# PP-Rev2.net
KiCad netlist of a schematic drawn in EAGLE
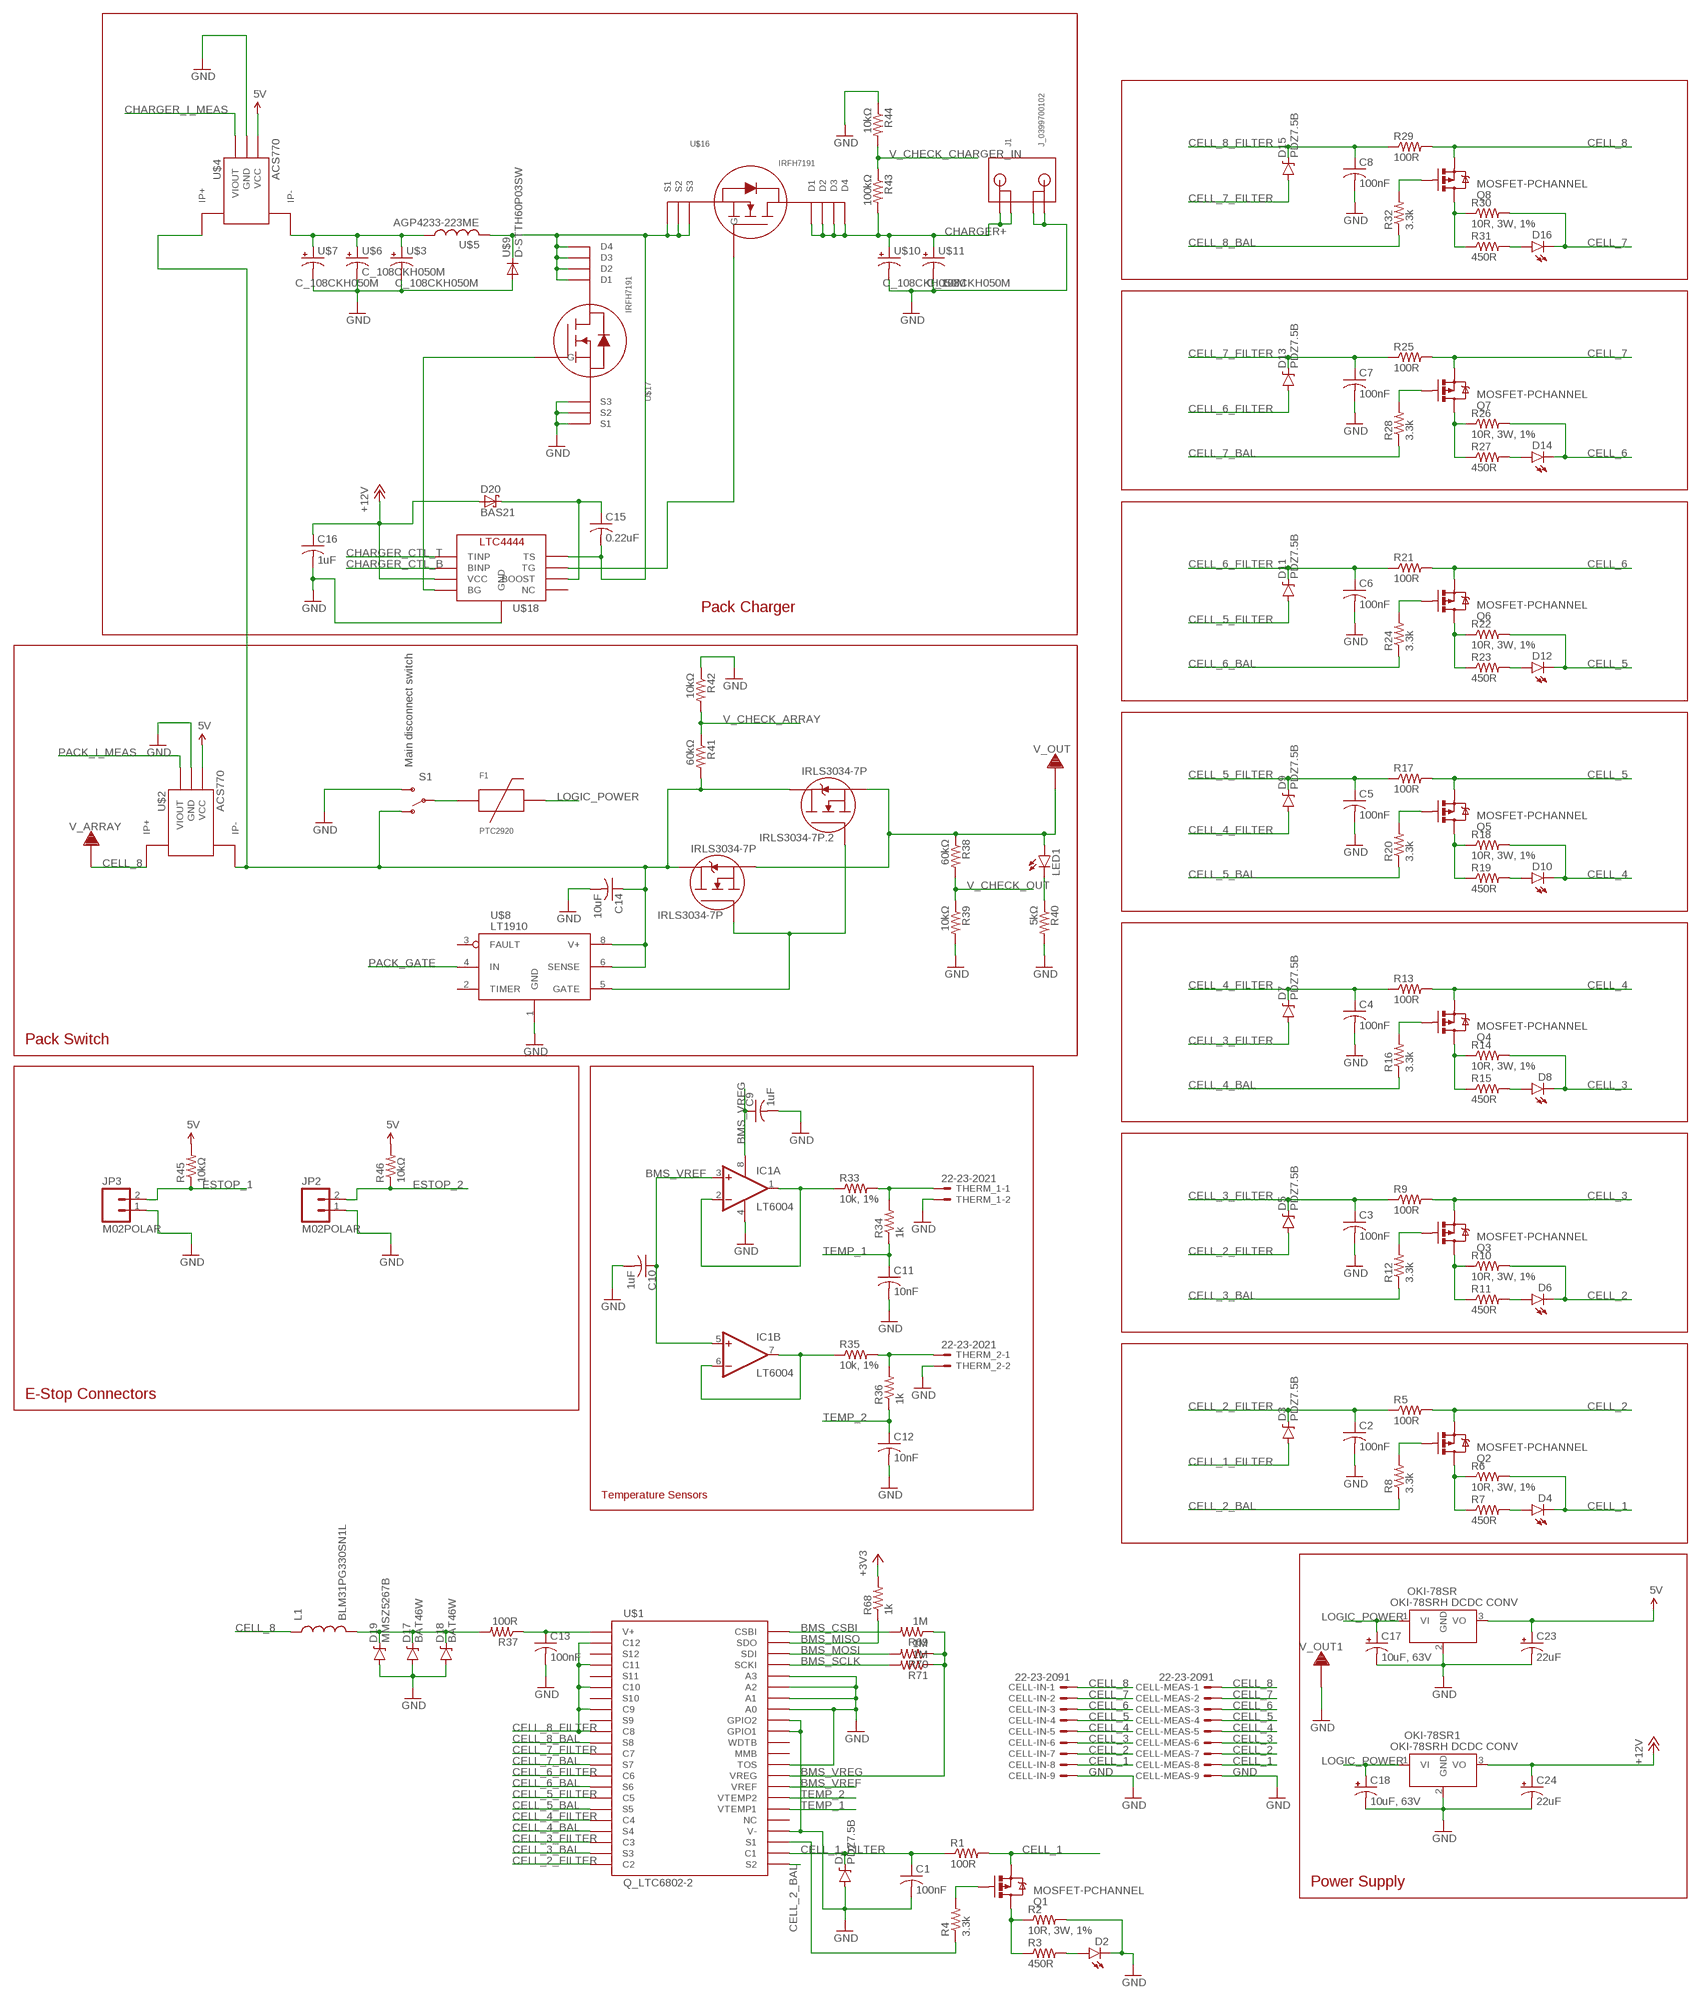
[diagram p0: schematic, sheet 1, part 1 of 2]
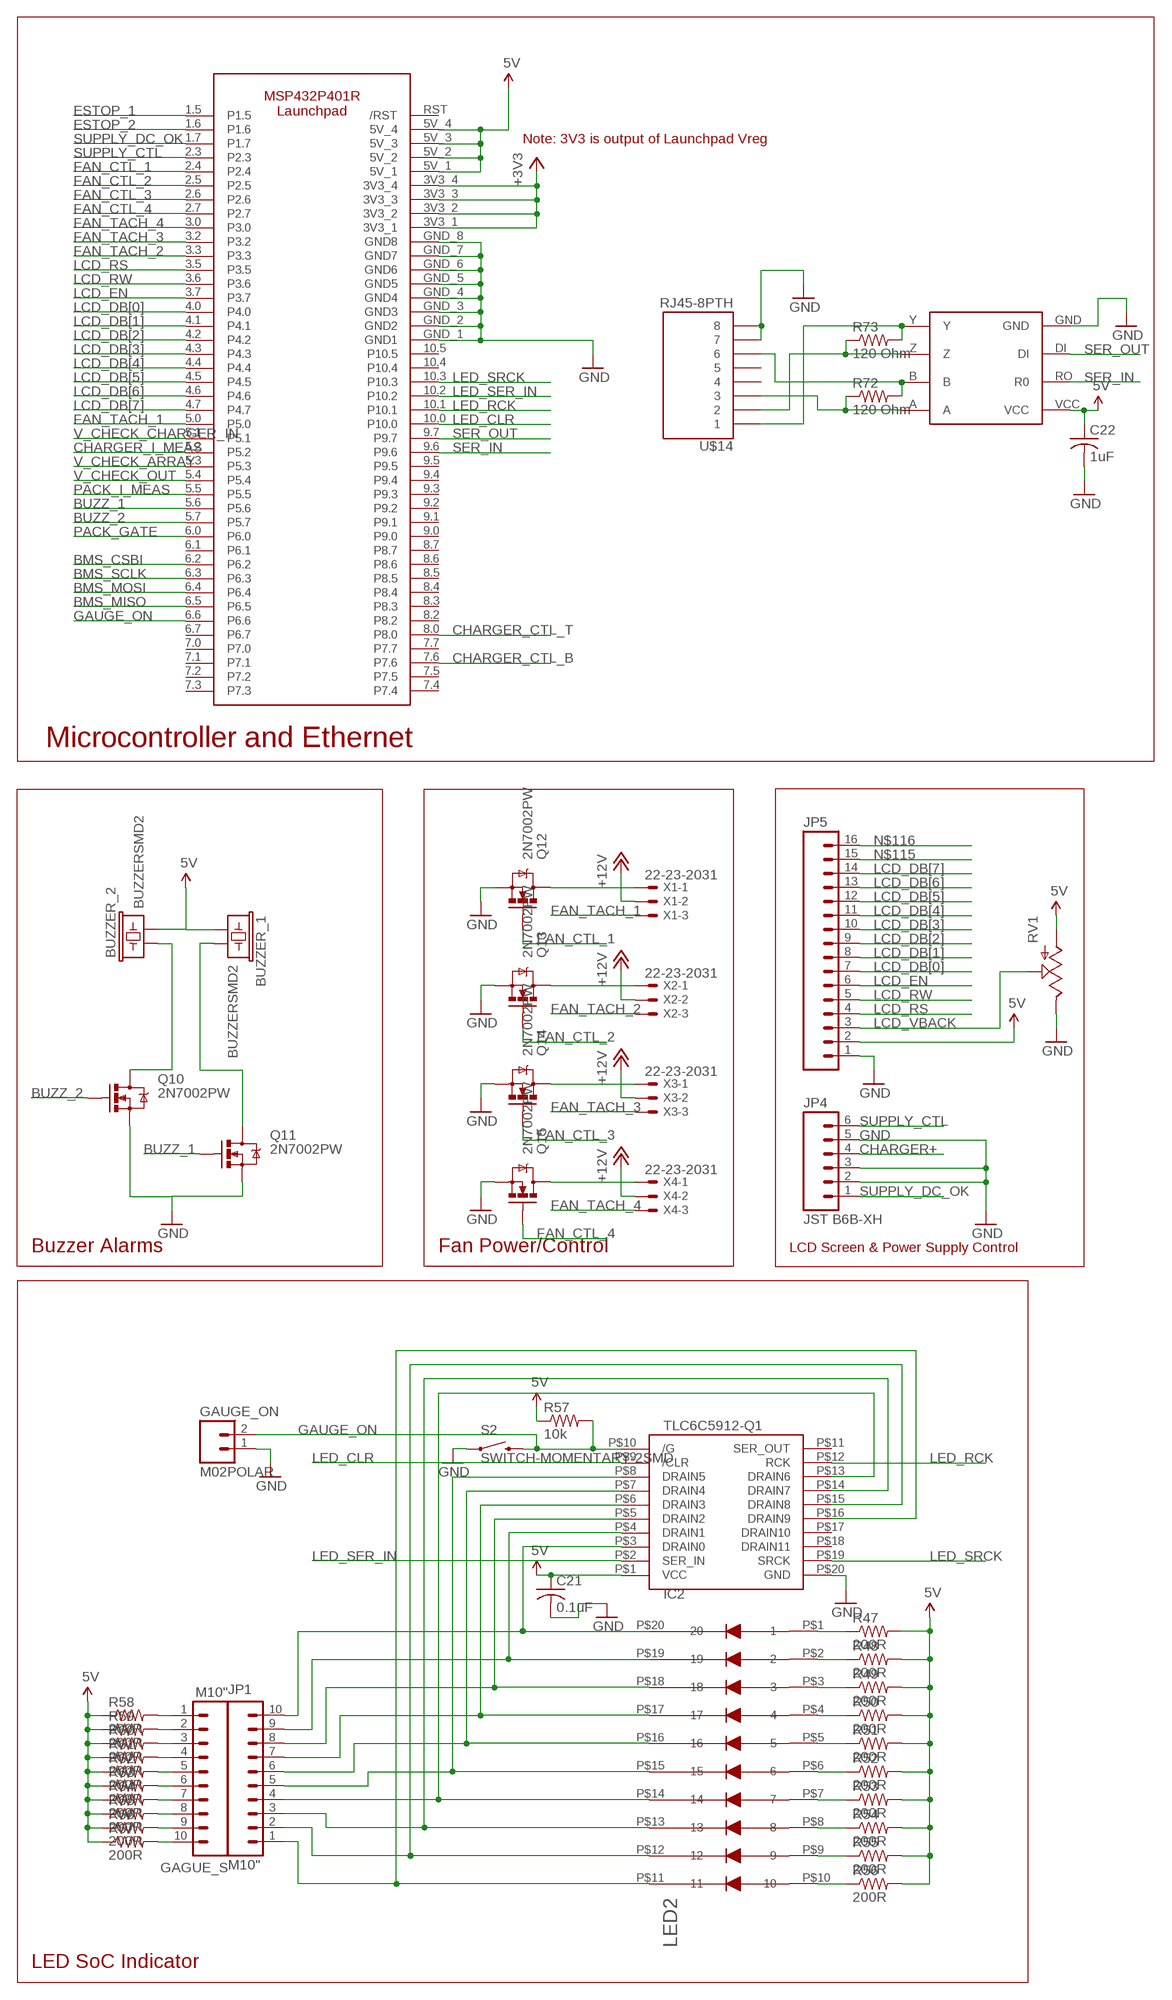
[diagram p1: schematic, sheet 1, part 2 of 2]

(export (version "E")
  (design (tool "Eeschema 10.0.6"))
  (components
    (comp (ref "BUZZER_1")
      (value "BUZZERSMD2")
      (footprint "eagle-import:BUZZER-CCV")
      (libsource (lib "eagle-import") (part "BUZZERSMD2"))
    )
    (comp (ref "BUZZER_2")
      (value "BUZZERSMD2")
      (footprint "eagle-import:BUZZER-CCV")
      (libsource (lib "eagle-import") (part "BUZZERSMD2"))
    )
    (comp (ref "C1")
      (value "100nF")
      (footprint "eagle-import:C1206")
      (libsource (lib "eagle-import") (part "C-USC1206"))
    )
    (comp (ref "C2")
      (value "100nF")
      (footprint "eagle-import:C1206")
      (libsource (lib "eagle-import") (part "C-USC1206"))
    )
    (comp (ref "C3")
      (value "100nF")
      (footprint "eagle-import:C1206")
      (libsource (lib "eagle-import") (part "C-USC1206"))
    )
    (comp (ref "C4")
      (value "100nF")
      (footprint "eagle-import:C1206")
      (libsource (lib "eagle-import") (part "C-USC1206"))
    )
    (comp (ref "C5")
      (value "100nF")
      (footprint "eagle-import:C1206")
      (libsource (lib "eagle-import") (part "C-USC1206"))
    )
    (comp (ref "C6")
      (value "100nF")
      (footprint "eagle-import:C1206")
      (libsource (lib "eagle-import") (part "C-USC1206"))
    )
    (comp (ref "C7")
      (value "100nF")
      (footprint "eagle-import:C1206")
      (libsource (lib "eagle-import") (part "C-USC1206"))
    )
    (comp (ref "C8")
      (value "100nF")
      (footprint "eagle-import:C1206")
      (libsource (lib "eagle-import") (part "C-USC1206"))
    )
    (comp (ref "C9")
      (value "1uF")
      (footprint "eagle-import:C1206")
      (libsource (lib "eagle-import") (part "C-USC1206"))
    )
    (comp (ref "C10")
      (value "1uF")
      (footprint "eagle-import:C1206")
      (libsource (lib "eagle-import") (part "C-USC1206"))
    )
    (comp (ref "C11")
      (value "10nF")
      (footprint "eagle-import:C1206")
      (libsource (lib "eagle-import") (part "C-USC1206"))
    )
    (comp (ref "C12")
      (value "10nF")
      (footprint "eagle-import:C1206")
      (libsource (lib "eagle-import") (part "C-USC1206"))
    )
    (comp (ref "C13")
      (value "100nF")
      (footprint "eagle-import:C1206")
      (libsource (lib "eagle-import") (part "C-USC1206"))
    )
    (comp (ref "C14")
      (value "10uF")
      (footprint "eagle-import:C1206")
      (libsource (lib "eagle-import") (part "C-USC1206"))
    )
    (comp (ref "C15")
      (value "0.22uF")
      (footprint "eagle-import:C1206")
      (libsource (lib "eagle-import") (part "C-USC1206"))
    )
    (comp (ref "C16")
      (value "1uF")
      (footprint "eagle-import:C1206")
      (libsource (lib "eagle-import") (part "C-USC1206"))
    )
    (comp (ref "C17")
      (value "10uF, 63V")
      (footprint "eagle-import:PANASONIC_D")
      (libsource (lib "eagle-import") (part "CPOL-USD"))
    )
    (comp (ref "C18")
      (value "10uF, 63V")
      (footprint "eagle-import:PANASONIC_D")
      (libsource (lib "eagle-import") (part "CPOL-USD"))
    )
    (comp (ref "C21")
      (value "0.1uF")
      (footprint "eagle-import:C1206")
      (libsource (lib "eagle-import") (part "resistor_C-USC1206"))
    )
    (comp (ref "C22")
      (value "1uF")
      (footprint "eagle-import:C1206")
      (libsource (lib "eagle-import") (part "resistor_C-USC1206"))
    )
    (comp (ref "C23")
      (value "22uF")
      (footprint "eagle-import:PANASONIC_D")
      (libsource (lib "eagle-import") (part "CPOL-USD"))
    )
    (comp (ref "C24")
      (value "22uF")
      (footprint "eagle-import:PANASONIC_D")
      (libsource (lib "eagle-import") (part "CPOL-USD"))
    )
    (comp (ref "CELL-IN")
      (value "22-23-2091")
      (footprint "eagle-import:22-23-2091")
      (fields (field (name "MF") "MOLEX"))
      (libsource (lib "eagle-import") (part "22-23-2091"))
    )
    (comp (ref "CELL-MEAS")
      (value "22-23-2091")
      (footprint "eagle-import:22-23-2091")
      (fields (field (name "MF") "MOLEX"))
      (libsource (lib "eagle-import") (part "22-23-2091"))
    )
    (comp (ref "D1")
      (value "PDZ7.5B")
      (footprint "eagle-import:SOD-323")
      (libsource (lib "eagle-import") (part "DIODE-ZENER5.6V"))
    )
    (comp (ref "D2")
      (value "LED1206")
      (footprint "eagle-import:LED-1206")
      (libsource (lib "eagle-import") (part "LED1206"))
    )
    (comp (ref "D3")
      (value "PDZ7.5B")
      (footprint "eagle-import:SOD-323")
      (libsource (lib "eagle-import") (part "DIODE-ZENER5.6V"))
    )
    (comp (ref "D4")
      (value "LED1206")
      (footprint "eagle-import:LED-1206")
      (libsource (lib "eagle-import") (part "LED1206"))
    )
    (comp (ref "D5")
      (value "PDZ7.5B")
      (footprint "eagle-import:SOD-323")
      (libsource (lib "eagle-import") (part "DIODE-ZENER5.6V"))
    )
    (comp (ref "D6")
      (value "LED1206")
      (footprint "eagle-import:LED-1206")
      (libsource (lib "eagle-import") (part "LED1206"))
    )
    (comp (ref "D7")
      (value "PDZ7.5B")
      (footprint "eagle-import:SOD-323")
      (libsource (lib "eagle-import") (part "DIODE-ZENER5.6V"))
    )
    (comp (ref "D8")
      (value "LED1206")
      (footprint "eagle-import:LED-1206")
      (libsource (lib "eagle-import") (part "LED1206"))
    )
    (comp (ref "D9")
      (value "PDZ7.5B")
      (footprint "eagle-import:SOD-323")
      (libsource (lib "eagle-import") (part "DIODE-ZENER5.6V"))
    )
    (comp (ref "D10")
      (value "LED1206")
      (footprint "eagle-import:LED-1206")
      (libsource (lib "eagle-import") (part "LED1206"))
    )
    (comp (ref "D11")
      (value "PDZ7.5B")
      (footprint "eagle-import:SOD-323")
      (libsource (lib "eagle-import") (part "DIODE-ZENER5.6V"))
    )
    (comp (ref "D12")
      (value "LED1206")
      (footprint "eagle-import:LED-1206")
      (libsource (lib "eagle-import") (part "LED1206"))
    )
    (comp (ref "D13")
      (value "PDZ7.5B")
      (footprint "eagle-import:SOD-323")
      (libsource (lib "eagle-import") (part "DIODE-ZENER5.6V"))
    )
    (comp (ref "D14")
      (value "LED1206")
      (footprint "eagle-import:LED-1206")
      (libsource (lib "eagle-import") (part "LED1206"))
    )
    (comp (ref "D15")
      (value "PDZ7.5B")
      (footprint "eagle-import:SOD-323")
      (libsource (lib "eagle-import") (part "DIODE-ZENER5.6V"))
    )
    (comp (ref "D16")
      (value "LED1206")
      (footprint "eagle-import:LED-1206")
      (libsource (lib "eagle-import") (part "LED1206"))
    )
    (comp (ref "D17")
      (value "BAT46W")
      (footprint "eagle-import:SOD-123")
      (libsource (lib "eagle-import") (part "DIODE-ZENER16V"))
    )
    (comp (ref "D18")
      (value "BAT46W")
      (footprint "eagle-import:SOD-123")
      (libsource (lib "eagle-import") (part "DIODE-ZENER16V"))
    )
    (comp (ref "D19")
      (value "MMSZ5267B")
      (footprint "eagle-import:SOD-123")
      (libsource (lib "eagle-import") (part "DIODE-ZENER16V"))
    )
    (comp (ref "D20")
      (value "BAS21")
      (footprint "eagle-import:SOT23")
      (libsource (lib "eagle-import") (part "BAS40"))
    )
    (comp (ref "F1")
      (value "PTC2920")
      (footprint "eagle-import:2920")
      (libsource (lib "eagle-import") (part "PTC2920"))
    )
    (comp (ref "GAGUE_S")
      (value "M10\"")
      (footprint "eagle-import:1X10")
      (libsource (lib "eagle-import") (part "M10{dblquote}"))
    )
    (comp (ref "GAUGE_ON")
      (value "M02POLAR")
      (footprint "eagle-import:MOLEX-1X2")
      (libsource (lib "eagle-import") (part "M02POLAR"))
    )
    (comp (ref "IC1")
      (value "LT6004")
      (footprint "eagle-import:MSOP08")
      (libsource (lib "eagle-import") (part "OPA2E345"))
    )
    (comp (ref "IC2")
      (value "TLC6C5912-Q1")
      (footprint "eagle-import:SOIC-20")
      (libsource (lib "eagle-import") (part "TLC6C5912-Q1"))
    )
    (comp (ref "IRLS3034-7P")
      (value "IRLS3034-7P")
      (footprint "eagle-import:D2PAK-7")
      (libsource (lib "eagle-import") (part "IRLS3034-7P"))
    )
    (comp (ref "IRLS3034-7P.2")
      (value "IRLS3034-7P")
      (footprint "eagle-import:D2PAK-7")
      (libsource (lib "eagle-import") (part "IRLS3034-7P"))
    )
    (comp (ref "J1")
      (value "J_0399700102")
      (footprint "eagle-import:J_2CONHC")
      (libsource (lib "eagle-import") (part "J_0399700102"))
    )
    (comp (ref "JP1")
      (value "M10\"")
      (footprint "eagle-import:1X10")
      (libsource (lib "eagle-import") (part "M10{dblquote}"))
    )
    (comp (ref "JP2")
      (value "M02POLAR")
      (footprint "eagle-import:MOLEX-1X2")
      (libsource (lib "eagle-import") (part "M02POLAR"))
    )
    (comp (ref "JP3")
      (value "M02POLAR")
      (footprint "eagle-import:MOLEX-1X2")
      (libsource (lib "eagle-import") (part "M02POLAR"))
    )
    (comp (ref "JP4")
      (value "JST B6B-XH")
      (footprint "eagle-import:MOLEX-1X6")
      (libsource (lib "eagle-import") (part "M06POLAR"))
    )
    (comp (ref "JP5")
      (value "M16LONGPADS")
      (footprint "eagle-import:1X16_LONGPADS")
      (libsource (lib "eagle-import") (part "M16LONGPADS"))
    )
    (comp (ref "L1")
      (value "BLM31PG330SN1L")
      (footprint "eagle-import:1210")
      (libsource (lib "eagle-import") (part "INDUCTOR1210"))
    )
    (comp (ref "LED1")
      (value "LED1206")
      (footprint "eagle-import:LED-1206")
      (libsource (lib "eagle-import") (part "LED1206"))
    )
    (comp (ref "LED2")
      (value "LED-DC7G3HWA")
      (footprint "eagle-import:LED-10")
      (libsource (lib "eagle-import") (part "LED-DC7G3HWA"))
    )
    (comp (ref "OKI-78SR")
      (value "Q_OKI-78SR5")
      (footprint "eagle-import:OKI-78SRH")
      (libsource (lib "eagle-import") (part "Q_OKI-78SR"))
    )
    (comp (ref "OKI-78SR1")
      (value "Q_OKI-78SR12")
      (footprint "eagle-import:OKI-78SRH")
      (libsource (lib "eagle-import") (part "Q_OKI-78SR"))
    )
    (comp (ref "Q1")
      (value "MOSFET-PCHANNEL")
      (footprint "eagle-import:SOT23-3")
      (libsource (lib "eagle-import") (part "MOSFET-PCHANNEL"))
    )
    (comp (ref "Q2")
      (value "MOSFET-PCHANNEL")
      (footprint "eagle-import:SOT23-3")
      (libsource (lib "eagle-import") (part "MOSFET-PCHANNEL"))
    )
    (comp (ref "Q3")
      (value "MOSFET-PCHANNEL")
      (footprint "eagle-import:SOT23-3")
      (libsource (lib "eagle-import") (part "MOSFET-PCHANNEL"))
    )
    (comp (ref "Q4")
      (value "MOSFET-PCHANNEL")
      (footprint "eagle-import:SOT23-3")
      (libsource (lib "eagle-import") (part "MOSFET-PCHANNEL"))
    )
    (comp (ref "Q5")
      (value "MOSFET-PCHANNEL")
      (footprint "eagle-import:SOT23-3")
      (libsource (lib "eagle-import") (part "MOSFET-PCHANNEL"))
    )
    (comp (ref "Q6")
      (value "MOSFET-PCHANNEL")
      (footprint "eagle-import:SOT23-3")
      (libsource (lib "eagle-import") (part "MOSFET-PCHANNEL"))
    )
    (comp (ref "Q7")
      (value "MOSFET-PCHANNEL")
      (footprint "eagle-import:SOT23-3")
      (libsource (lib "eagle-import") (part "MOSFET-PCHANNEL"))
    )
    (comp (ref "Q8")
      (value "MOSFET-PCHANNEL")
      (footprint "eagle-import:SOT23-3")
      (libsource (lib "eagle-import") (part "MOSFET-PCHANNEL"))
    )
    (comp (ref "Q10")
      (value "2N7002PW")
      (footprint "eagle-import:SOT323")
      (libsource (lib "eagle-import") (part "MOSFET-NCHANNEL2N7002PW"))
    )
    (comp (ref "Q11")
      (value "2N7002PW")
      (footprint "eagle-import:SOT323")
      (libsource (lib "eagle-import") (part "MOSFET-NCHANNEL2N7002PW"))
    )
    (comp (ref "Q12")
      (value "2N7002PW")
      (footprint "eagle-import:SOT323")
      (libsource (lib "eagle-import") (part "MOSFET-NCHANNEL2N7002PW"))
    )
    (comp (ref "Q13")
      (value "2N7002PW")
      (footprint "eagle-import:SOT323")
      (libsource (lib "eagle-import") (part "MOSFET-NCHANNEL2N7002PW"))
    )
    (comp (ref "Q14")
      (value "2N7002PW")
      (footprint "eagle-import:SOT323")
      (libsource (lib "eagle-import") (part "MOSFET-NCHANNEL2N7002PW"))
    )
    (comp (ref "Q15")
      (value "2N7002PW")
      (footprint "eagle-import:SOT323")
      (libsource (lib "eagle-import") (part "MOSFET-NCHANNEL2N7002PW"))
    )
    (comp (ref "R1")
      (value "100R")
      (footprint "eagle-import:R1206")
      (libsource (lib "eagle-import") (part "R-US_R1206"))
    )
    (comp (ref "R2")
      (value "10R, 3W, 1%")
      (footprint "eagle-import:AXIAL-0.6")
      (libsource (lib "eagle-import") (part "SparkFun-Resistors_RESISTORPTH-1W"))
    )
    (comp (ref "R3")
      (value "450R")
      (footprint "eagle-import:1206")
      (libsource (lib "eagle-import") (part "SparkFun-Resistors_RESISTOR1206"))
    )
    (comp (ref "R4")
      (value "3.3k")
      (footprint "eagle-import:1206")
      (libsource (lib "eagle-import") (part "SparkFun-Resistors_RESISTOR1206"))
    )
    (comp (ref "R5")
      (value "100R")
      (footprint "eagle-import:R1206")
      (libsource (lib "eagle-import") (part "R-US_R1206"))
    )
    (comp (ref "R6")
      (value "10R, 3W, 1%")
      (footprint "eagle-import:AXIAL-0.6")
      (libsource (lib "eagle-import") (part "SparkFun-Resistors_RESISTORPTH-1W"))
    )
    (comp (ref "R7")
      (value "450R")
      (footprint "eagle-import:1206")
      (libsource (lib "eagle-import") (part "SparkFun-Resistors_RESISTOR1206"))
    )
    (comp (ref "R8")
      (value "3.3k")
      (footprint "eagle-import:1206")
      (libsource (lib "eagle-import") (part "SparkFun-Resistors_RESISTOR1206"))
    )
    (comp (ref "R9")
      (value "100R")
      (footprint "eagle-import:R1206")
      (libsource (lib "eagle-import") (part "R-US_R1206"))
    )
    (comp (ref "R10")
      (value "10R, 3W, 1%")
      (footprint "eagle-import:AXIAL-0.6")
      (libsource (lib "eagle-import") (part "SparkFun-Resistors_RESISTORPTH-1W"))
    )
    (comp (ref "R11")
      (value "450R")
      (footprint "eagle-import:1206")
      (libsource (lib "eagle-import") (part "SparkFun-Resistors_RESISTOR1206"))
    )
    (comp (ref "R12")
      (value "3.3k")
      (footprint "eagle-import:1206")
      (libsource (lib "eagle-import") (part "SparkFun-Resistors_RESISTOR1206"))
    )
    (comp (ref "R13")
      (value "100R")
      (footprint "eagle-import:R1206")
      (libsource (lib "eagle-import") (part "R-US_R1206"))
    )
    (comp (ref "R14")
      (value "10R, 3W, 1%")
      (footprint "eagle-import:AXIAL-0.6")
      (libsource (lib "eagle-import") (part "SparkFun-Resistors_RESISTORPTH-1W"))
    )
    (comp (ref "R15")
      (value "450R")
      (footprint "eagle-import:1206")
      (libsource (lib "eagle-import") (part "SparkFun-Resistors_RESISTOR1206"))
    )
    (comp (ref "R16")
      (value "3.3k")
      (footprint "eagle-import:1206")
      (libsource (lib "eagle-import") (part "SparkFun-Resistors_RESISTOR1206"))
    )
    (comp (ref "R17")
      (value "100R")
      (footprint "eagle-import:R1206")
      (libsource (lib "eagle-import") (part "R-US_R1206"))
    )
    (comp (ref "R18")
      (value "10R, 3W, 1%")
      (footprint "eagle-import:AXIAL-0.6")
      (libsource (lib "eagle-import") (part "SparkFun-Resistors_RESISTORPTH-1W"))
    )
    (comp (ref "R19")
      (value "450R")
      (footprint "eagle-import:1206")
      (libsource (lib "eagle-import") (part "SparkFun-Resistors_RESISTOR1206"))
    )
    (comp (ref "R20")
      (value "3.3k")
      (footprint "eagle-import:1206")
      (libsource (lib "eagle-import") (part "SparkFun-Resistors_RESISTOR1206"))
    )
    (comp (ref "R21")
      (value "100R")
      (footprint "eagle-import:R1206")
      (libsource (lib "eagle-import") (part "R-US_R1206"))
    )
    (comp (ref "R22")
      (value "10R, 3W, 1%")
      (footprint "eagle-import:AXIAL-0.6")
      (libsource (lib "eagle-import") (part "SparkFun-Resistors_RESISTORPTH-1W"))
    )
    (comp (ref "R23")
      (value "450R")
      (footprint "eagle-import:1206")
      (libsource (lib "eagle-import") (part "SparkFun-Resistors_RESISTOR1206"))
    )
    (comp (ref "R24")
      (value "3.3k")
      (footprint "eagle-import:1206")
      (libsource (lib "eagle-import") (part "SparkFun-Resistors_RESISTOR1206"))
    )
    (comp (ref "R25")
      (value "100R")
      (footprint "eagle-import:R1206")
      (libsource (lib "eagle-import") (part "R-US_R1206"))
    )
    (comp (ref "R26")
      (value "10R, 3W, 1%")
      (footprint "eagle-import:AXIAL-0.6")
      (libsource (lib "eagle-import") (part "SparkFun-Resistors_RESISTORPTH-1W"))
    )
    (comp (ref "R27")
      (value "450R")
      (footprint "eagle-import:1206")
      (libsource (lib "eagle-import") (part "SparkFun-Resistors_RESISTOR1206"))
    )
    (comp (ref "R28")
      (value "3.3k")
      (footprint "eagle-import:1206")
      (libsource (lib "eagle-import") (part "SparkFun-Resistors_RESISTOR1206"))
    )
    (comp (ref "R29")
      (value "100R")
      (footprint "eagle-import:R1206")
      (libsource (lib "eagle-import") (part "R-US_R1206"))
    )
    (comp (ref "R30")
      (value "10R, 3W, 1%")
      (footprint "eagle-import:AXIAL-0.6")
      (libsource (lib "eagle-import") (part "SparkFun-Resistors_RESISTORPTH-1W"))
    )
    (comp (ref "R31")
      (value "450R")
      (footprint "eagle-import:1206")
      (libsource (lib "eagle-import") (part "SparkFun-Resistors_RESISTOR1206"))
    )
    (comp (ref "R32")
      (value "3.3k")
      (footprint "eagle-import:1206")
      (libsource (lib "eagle-import") (part "SparkFun-Resistors_RESISTOR1206"))
    )
    (comp (ref "R33")
      (value "10k, 1%")
      (footprint "eagle-import:R1206")
      (libsource (lib "eagle-import") (part "R-US_R1206"))
    )
    (comp (ref "R34")
      (value "1k")
      (footprint "eagle-import:R1206")
      (libsource (lib "eagle-import") (part "R-US_R1206"))
    )
    (comp (ref "R35")
      (value "10k, 1%")
      (footprint "eagle-import:R1206")
      (libsource (lib "eagle-import") (part "R-US_R1206"))
    )
    (comp (ref "R36")
      (value "1k")
      (footprint "eagle-import:R1206")
      (libsource (lib "eagle-import") (part "R-US_R1206"))
    )
    (comp (ref "R37")
      (value "100R")
      (footprint "eagle-import:R1206")
      (libsource (lib "eagle-import") (part "R-US_R1206"))
    )
    (comp (ref "R38")
      (value "60kΩ")
      (footprint "eagle-import:R1206")
      (libsource (lib "eagle-import") (part "resistor_R-US_R1206"))
    )
    (comp (ref "R39")
      (value "10kΩ")
      (footprint "eagle-import:R1206")
      (libsource (lib "eagle-import") (part "resistor_R-US_R1206"))
    )
    (comp (ref "R40")
      (value "5kΩ")
      (footprint "eagle-import:R1206")
      (libsource (lib "eagle-import") (part "resistor_R-US_R1206"))
    )
    (comp (ref "R41")
      (value "60kΩ")
      (footprint "eagle-import:R1206")
      (libsource (lib "eagle-import") (part "resistor_R-US_R1206"))
    )
    (comp (ref "R42")
      (value "10kΩ")
      (footprint "eagle-import:R1206")
      (libsource (lib "eagle-import") (part "resistor_R-US_R1206"))
    )
    (comp (ref "R43")
      (value "100kΩ")
      (footprint "eagle-import:R1206")
      (libsource (lib "eagle-import") (part "resistor_R-US_R1206"))
    )
    (comp (ref "R44")
      (value "10kΩ")
      (footprint "eagle-import:R1206")
      (libsource (lib "eagle-import") (part "resistor_R-US_R1206"))
    )
    (comp (ref "R45")
      (value "10kΩ")
      (footprint "eagle-import:R1206")
      (libsource (lib "eagle-import") (part "resistor_R-US_R1206"))
    )
    (comp (ref "R46")
      (value "10kΩ")
      (footprint "eagle-import:R1206")
      (libsource (lib "eagle-import") (part "resistor_R-US_R1206"))
    )
    (comp (ref "R47")
      (value "200R")
      (footprint "eagle-import:R1206")
      (libsource (lib "eagle-import") (part "R-US_R1206"))
    )
    (comp (ref "R48")
      (value "200R")
      (footprint "eagle-import:R1206")
      (libsource (lib "eagle-import") (part "R-US_R1206"))
    )
    (comp (ref "R49")
      (value "200R")
      (footprint "eagle-import:R1206")
      (libsource (lib "eagle-import") (part "R-US_R1206"))
    )
    (comp (ref "R50")
      (value "200R")
      (footprint "eagle-import:R1206")
      (libsource (lib "eagle-import") (part "R-US_R1206"))
    )
    (comp (ref "R51")
      (value "200R")
      (footprint "eagle-import:R1206")
      (libsource (lib "eagle-import") (part "R-US_R1206"))
    )
    (comp (ref "R52")
      (value "200R")
      (footprint "eagle-import:R1206")
      (libsource (lib "eagle-import") (part "R-US_R1206"))
    )
    (comp (ref "R53")
      (value "200R")
      (footprint "eagle-import:R1206")
      (libsource (lib "eagle-import") (part "R-US_R1206"))
    )
    (comp (ref "R54")
      (value "200R")
      (footprint "eagle-import:R1206")
      (libsource (lib "eagle-import") (part "R-US_R1206"))
    )
    (comp (ref "R55")
      (value "200R")
      (footprint "eagle-import:R1206")
      (libsource (lib "eagle-import") (part "R-US_R1206"))
    )
    (comp (ref "R56")
      (value "200R")
      (footprint "eagle-import:R1206")
      (libsource (lib "eagle-import") (part "R-US_R1206"))
    )
    (comp (ref "R57")
      (value "10k")
      (footprint "eagle-import:R1206")
      (libsource (lib "eagle-import") (part "R-US_R1206"))
    )
    (comp (ref "R58")
      (value "200R")
      (footprint "eagle-import:R1206")
      (libsource (lib "eagle-import") (part "R-US_R1206"))
    )
    (comp (ref "R59")
      (value "200R")
      (footprint "eagle-import:R1206")
      (libsource (lib "eagle-import") (part "R-US_R1206"))
    )
    (comp (ref "R60")
      (value "200R")
      (footprint "eagle-import:R1206")
      (libsource (lib "eagle-import") (part "R-US_R1206"))
    )
    (comp (ref "R61")
      (value "200R")
      (footprint "eagle-import:R1206")
      (libsource (lib "eagle-import") (part "R-US_R1206"))
    )
    (comp (ref "R62")
      (value "200R")
      (footprint "eagle-import:R1206")
      (libsource (lib "eagle-import") (part "R-US_R1206"))
    )
    (comp (ref "R63")
      (value "200R")
      (footprint "eagle-import:R1206")
      (libsource (lib "eagle-import") (part "R-US_R1206"))
    )
    (comp (ref "R64")
      (value "200R")
      (footprint "eagle-import:R1206")
      (libsource (lib "eagle-import") (part "R-US_R1206"))
    )
    (comp (ref "R65")
      (value "200R")
      (footprint "eagle-import:R1206")
      (libsource (lib "eagle-import") (part "R-US_R1206"))
    )
    (comp (ref "R66")
      (value "200R")
      (footprint "eagle-import:R1206")
      (libsource (lib "eagle-import") (part "R-US_R1206"))
    )
    (comp (ref "R67")
      (value "200R")
      (footprint "eagle-import:R1206")
      (libsource (lib "eagle-import") (part "R-US_R1206"))
    )
    (comp (ref "R68")
      (value "1k")
      (footprint "eagle-import:R1206")
      (libsource (lib "eagle-import") (part "R-US_R1206"))
    )
    (comp (ref "R69")
      (value "1M")
      (footprint "eagle-import:R1206")
      (libsource (lib "eagle-import") (part "R-US_R1206"))
    )
    (comp (ref "R70")
      (value "1M")
      (footprint "eagle-import:R1206")
      (libsource (lib "eagle-import") (part "R-US_R1206"))
    )
    (comp (ref "R71")
      (value "1M")
      (footprint "eagle-import:R1206")
      (libsource (lib "eagle-import") (part "R-US_R1206"))
    )
    (comp (ref "R72")
      (value "120 Ohm")
      (footprint "eagle-import:1206")
      (libsource (lib "eagle-import") (part "RESISTOR1206"))
    )
    (comp (ref "R73")
      (value "120 Ohm")
      (footprint "eagle-import:1206")
      (libsource (lib "eagle-import") (part "RESISTOR1206"))
    )
    (comp (ref "RV1")
      (value "POTTRIM")
      (footprint "eagle-import:TRIM_POT")
      (libsource (lib "eagle-import") (part "POTTRIM"))
    )
    (comp (ref "S1")
      (value "SWITCH-SPDTPTH")
      (footprint "eagle-import:SWITCH-SPDT")
      (libsource (lib "eagle-import") (part "SWITCH-SPDTPTH"))
    )
    (comp (ref "S2")
      (value "SWITCH-MOMENTARY-2SMD")
      (footprint "eagle-import:TACTILE-SWITCH-SMD")
      (libsource (lib "eagle-import") (part "SWITCH-MOMENTARY-2SMD"))
    )
    (comp (ref "THERM_1")
      (value "22-23-2021")
      (footprint "eagle-import:22-23-2021")
      (fields (field (name "MF") "MOLEX"))
      (libsource (lib "eagle-import") (part "22-23-2021"))
    )
    (comp (ref "THERM_2")
      (value "22-23-2021")
      (footprint "eagle-import:22-23-2021")
      (fields (field (name "MF") "MOLEX"))
      (libsource (lib "eagle-import") (part "22-23-2021"))
    )
    (comp (ref "U$1")
      (value "Q_LTC6802-2")
      (footprint "eagle-import:SSOP44")
      (libsource (lib "eagle-import") (part "Q_LTC6802-2"))
    )
    (comp (ref "U$2")
      (value "ACS770")
      (footprint "eagle-import:PFF_LEADFORM")
      (libsource (lib "eagle-import") (part "ACS770"))
    )
    (comp (ref "U$3")
      (value "C_108CKH050M")
      (footprint "eagle-import:C_16MM")
      (libsource (lib "eagle-import") (part "C_108CKH050M"))
    )
    (comp (ref "U$4")
      (value "ACS770")
      (footprint "eagle-import:PFF_LEADFORM")
      (libsource (lib "eagle-import") (part "ACS770"))
    )
    (comp (ref "U$5")
      (value "AGP4233-223ME")
      (footprint "eagle-import:AGP4233")
      (libsource (lib "eagle-import") (part "AGP4233"))
    )
    (comp (ref "U$6")
      (value "C_108CKH050M")
      (footprint "eagle-import:C_16MM")
      (libsource (lib "eagle-import") (part "C_108CKH050M"))
    )
    (comp (ref "U$7")
      (value "C_108CKH050M")
      (footprint "eagle-import:C_16MM")
      (libsource (lib "eagle-import") (part "C_108CKH050M"))
    )
    (comp (ref "U$8")
      (value "LT1910")
      (footprint "eagle-import:SO8")
      (libsource (lib "eagle-import") (part "LT1910"))
    )
    (comp (ref "U$9")
      (value "D-STTH60P03SW")
      (footprint "eagle-import:TO-247-VERT")
      (libsource (lib "eagle-import") (part "D-STTH60P03SW"))
    )
    (comp (ref "U$10")
      (value "C_108CKH050M")
      (footprint "eagle-import:C_16MM")
      (libsource (lib "eagle-import") (part "C_108CKH050M"))
    )
    (comp (ref "U$11")
      (value "C_108CKH050M")
      (footprint "eagle-import:C_16MM")
      (libsource (lib "eagle-import") (part "C_108CKH050M"))
    )
    (comp (ref "U$13")
      (value "MSP432P401R-LAUNCHPAD")
      (footprint "eagle-import:MSP432P401R-LAUNCHPAD")
      (libsource (lib "eagle-import") (part "MSP432P401R-LAUNCHPAD"))
    )
    (comp (ref "U$14")
      (value "RJ45-8PTH")
      (footprint "eagle-import:RJ45-8")
      (libsource (lib "eagle-import") (part "RJ45-8PTH"))
    )
    (comp (ref "U$15")
      (value "MAX3077")
      (footprint "eagle-import:MAX3070E")
      (libsource (lib "eagle-import") (part "MAX3077"))
    )
    (comp (ref "U$16")
      (value "IRFH7191")
      (footprint "eagle-import:PQFN5X6B")
      (libsource (lib "eagle-import") (part "IRFH7191"))
    )
    (comp (ref "U$17")
      (value "IRFH7191")
      (footprint "eagle-import:PQFN5X6B")
      (libsource (lib "eagle-import") (part "IRFH7191"))
    )
    (comp (ref "U$18")
      (value "LTC4444")
      (footprint "eagle-import:MS8E")
      (libsource (lib "eagle-import") (part "LTC4444"))
    )
    (comp (ref "V_ARRAY")
      (value "TERMINAL_HOLE")
      (footprint "eagle-import:LARGE_TERMINAL_HOLE")
      (libsource (lib "eagle-import") (part "TERMINAL_HOLE"))
    )
    (comp (ref "V_OUT")
      (value "TERMINAL_HOLE")
      (footprint "eagle-import:LARGE_TERMINAL_HOLE")
      (libsource (lib "eagle-import") (part "TERMINAL_HOLE"))
    )
    (comp (ref "V_OUT1")
      (value "TERMINAL_HOLE")
      (footprint "eagle-import:LARGE_TERMINAL_HOLE")
      (libsource (lib "eagle-import") (part "TERMINAL_HOLE"))
    )
    (comp (ref "X1")
      (value "22-23-2031")
      (footprint "eagle-import:22-23-2031")
      (fields (field (name "MF") "MOLEX"))
      (libsource (lib "eagle-import") (part "22-23-2031"))
    )
    (comp (ref "X2")
      (value "22-23-2031")
      (footprint "eagle-import:22-23-2031")
      (fields (field (name "MF") "MOLEX"))
      (libsource (lib "eagle-import") (part "22-23-2031"))
    )
    (comp (ref "X3")
      (value "22-23-2031")
      (footprint "eagle-import:22-23-2031")
      (fields (field (name "MF") "MOLEX"))
      (libsource (lib "eagle-import") (part "22-23-2031"))
    )
    (comp (ref "X4")
      (value "22-23-2031")
      (footprint "eagle-import:22-23-2031")
      (fields (field (name "MF") "MOLEX"))
      (libsource (lib "eagle-import") (part "22-23-2031"))
    )
  )
  (nets
    (net (code "1") (name "+3V3") (class "Default")
      (node (ref "R68") (pin "2") (pinfunction "2_2") (pintype "passive"))
      (node (ref "U$13") (pin "3V3_1") (pinfunction "3V3_1_3V3_1") (pintype "bidirectional"))
      (node (ref "U$13") (pin "3V3_2") (pinfunction "3V3_2_3V3_2") (pintype "bidirectional"))
      (node (ref "U$13") (pin "3V3_3") (pinfunction "3V3_3_3V3_3") (pintype "bidirectional"))
      (node (ref "U$13") (pin "3V3_4") (pinfunction "3V3_4_3V3_4") (pintype "bidirectional"))
    )
    (net (code "2") (name "+12V") (class "Default")
      (node (ref "C16") (pin "1") (pinfunction "1_1") (pintype "passive"))
      (node (ref "C24") (pin "+") (pinfunction "+_+") (pintype "passive"))
      (node (ref "D20") (pin "1") (pinfunction "A_1") (pintype "passive"))
      (node (ref "OKI-78SR1") (pin "3") (pinfunction "VO_3") (pintype "bidirectional"))
      (node (ref "U$18") (pin "P$3") (pinfunction "VCC_P$3") (pintype "bidirectional"))
      (node (ref "X1") (pin "2") (pinfunction "S_2") (pintype "passive"))
      (node (ref "X2") (pin "2") (pinfunction "S_2") (pintype "passive"))
      (node (ref "X3") (pin "2") (pinfunction "S_2") (pintype "passive"))
      (node (ref "X4") (pin "2") (pinfunction "S_2") (pintype "passive"))
    )
    (net (code "3") (name "/BMS_CSBI") (class "Default")
      (node (ref "R69") (pin "2") (pinfunction "2_2") (pintype "passive"))
      (node (ref "U$1") (pin "44") (pinfunction "CSBI_44") (pintype "bidirectional"))
      (node (ref "U$13") (pin "6.2") (pinfunction "P6.2_6.2") (pintype "bidirectional"))
    )
    (net (code "4") (name "/BMS_MISO") (class "Default")
      (node (ref "R68") (pin "1") (pinfunction "1_1") (pintype "passive"))
      (node (ref "U$1") (pin "43") (pinfunction "SDO_43") (pintype "bidirectional"))
      (node (ref "U$13") (pin "6.5") (pinfunction "P6.5_6.5") (pintype "bidirectional"))
    )
    (net (code "5") (name "/BMS_MOSI") (class "Default")
      (node (ref "R70") (pin "2") (pinfunction "2_2") (pintype "passive"))
      (node (ref "U$1") (pin "42") (pinfunction "SDI_42") (pintype "bidirectional"))
      (node (ref "U$13") (pin "6.4") (pinfunction "P6.4_6.4") (pintype "bidirectional"))
    )
    (net (code "6") (name "/BMS_SCLK") (class "Default")
      (node (ref "R71") (pin "2") (pinfunction "2_2") (pintype "passive"))
      (node (ref "U$1") (pin "41") (pinfunction "SCKI_41") (pintype "bidirectional"))
      (node (ref "U$13") (pin "6.3") (pinfunction "P6.3_6.3") (pintype "bidirectional"))
    )
    (net (code "7") (name "/BMS_VREF") (class "Default")
      (node (ref "C10") (pin "1") (pinfunction "1_1") (pintype "passive"))
      (node (ref "IC1") (pin "3") (pinfunction "+IN_3") (pintype "input"))
      (node (ref "IC1") (pin "5") (pinfunction "+IN_5") (pintype "input"))
      (node (ref "U$1") (pin "30") (pinfunction "VREF_30") (pintype "bidirectional"))
    )
    (net (code "8") (name "/BMS_VREG") (class "Default")
      (node (ref "C9") (pin "1") (pinfunction "1_1") (pintype "passive"))
      (node (ref "IC1") (pin "8") (pinfunction "V+_8") (pintype "power_in"))
      (node (ref "R69") (pin "1") (pinfunction "1_1") (pintype "passive"))
      (node (ref "R70") (pin "1") (pinfunction "1_1") (pintype "passive"))
      (node (ref "R71") (pin "1") (pinfunction "1_1") (pintype "passive"))
      (node (ref "U$1") (pin "31") (pinfunction "VREG_31") (pintype "bidirectional"))
    )
    (net (code "9") (name "/BUZZ_1") (class "Default")
      (node (ref "Q11") (pin "1") (pinfunction "G_1") (pintype "passive"))
      (node (ref "U$13") (pin "5.6") (pinfunction "P5.6_5.6") (pintype "bidirectional"))
    )
    (net (code "10") (name "/BUZZ_2") (class "Default")
      (node (ref "Q10") (pin "1") (pinfunction "G_1") (pintype "passive"))
      (node (ref "U$13") (pin "5.7") (pinfunction "P5.7_5.7") (pintype "bidirectional"))
    )
    (net (code "11") (name "/CELL_1") (class "Default")
      (node (ref "CELL-IN") (pin "8") (pinfunction "S_8") (pintype "passive"))
      (node (ref "CELL-MEAS") (pin "8") (pinfunction "S_8") (pintype "passive"))
      (node (ref "D4") (pin "C") (pinfunction "C_C") (pintype "passive"))
      (node (ref "Q1") (pin "2") (pinfunction "S_2") (pintype "passive"))
      (node (ref "R1") (pin "2") (pinfunction "2_2") (pintype "passive"))
      (node (ref "R6") (pin "P$2") (pinfunction "2_P$2") (pintype "passive"))
    )
    (net (code "12") (name "/CELL_1_FILTER") (class "Default")
      (node (ref "C1") (pin "1") (pinfunction "1_1") (pintype "passive"))
      (node (ref "D1") (pin "C") (pinfunction "C_C") (pintype "passive"))
      (node (ref "D3") (pin "A") (pinfunction "A_A") (pintype "passive"))
      (node (ref "R1") (pin "1") (pinfunction "1_1") (pintype "passive"))
      (node (ref "U$1") (pin "24") (pinfunction "C1_24") (pintype "bidirectional"))
    )
    (net (code "13") (name "/CELL_2") (class "Default")
      (node (ref "CELL-IN") (pin "7") (pinfunction "S_7") (pintype "passive"))
      (node (ref "CELL-MEAS") (pin "7") (pinfunction "S_7") (pintype "passive"))
      (node (ref "D6") (pin "C") (pinfunction "C_C") (pintype "passive"))
      (node (ref "Q2") (pin "2") (pinfunction "S_2") (pintype "passive"))
      (node (ref "R10") (pin "P$2") (pinfunction "2_P$2") (pintype "passive"))
      (node (ref "R5") (pin "2") (pinfunction "2_2") (pintype "passive"))
    )
    (net (code "14") (name "/CELL_2_BAL") (class "Default")
      (node (ref "R8") (pin "1") (pinfunction "1_1") (pintype "passive"))
      (node (ref "U$1") (pin "23") (pinfunction "S2_23") (pintype "bidirectional"))
    )
    (net (code "15") (name "/CELL_2_FILTER") (class "Default")
      (node (ref "C2") (pin "1") (pinfunction "1_1") (pintype "passive"))
      (node (ref "D3") (pin "C") (pinfunction "C_C") (pintype "passive"))
      (node (ref "D5") (pin "A") (pinfunction "A_A") (pintype "passive"))
      (node (ref "R5") (pin "1") (pinfunction "1_1") (pintype "passive"))
      (node (ref "U$1") (pin "22") (pinfunction "C2_22") (pintype "bidirectional"))
    )
    (net (code "16") (name "/CELL_3") (class "Default")
      (node (ref "CELL-IN") (pin "6") (pinfunction "S_6") (pintype "passive"))
      (node (ref "CELL-MEAS") (pin "6") (pinfunction "S_6") (pintype "passive"))
      (node (ref "D8") (pin "C") (pinfunction "C_C") (pintype "passive"))
      (node (ref "Q3") (pin "2") (pinfunction "S_2") (pintype "passive"))
      (node (ref "R14") (pin "P$2") (pinfunction "2_P$2") (pintype "passive"))
      (node (ref "R9") (pin "2") (pinfunction "2_2") (pintype "passive"))
    )
    (net (code "17") (name "/CELL_3_BAL") (class "Default")
      (node (ref "R12") (pin "1") (pinfunction "1_1") (pintype "passive"))
      (node (ref "U$1") (pin "21") (pinfunction "S3_21") (pintype "bidirectional"))
    )
    (net (code "18") (name "/CELL_3_FILTER") (class "Default")
      (node (ref "C3") (pin "1") (pinfunction "1_1") (pintype "passive"))
      (node (ref "D5") (pin "C") (pinfunction "C_C") (pintype "passive"))
      (node (ref "D7") (pin "A") (pinfunction "A_A") (pintype "passive"))
      (node (ref "R9") (pin "1") (pinfunction "1_1") (pintype "passive"))
      (node (ref "U$1") (pin "20") (pinfunction "C3_20") (pintype "bidirectional"))
    )
    (net (code "19") (name "/CELL_4") (class "Default")
      (node (ref "CELL-IN") (pin "5") (pinfunction "S_5") (pintype "passive"))
      (node (ref "CELL-MEAS") (pin "5") (pinfunction "S_5") (pintype "passive"))
      (node (ref "D10") (pin "C") (pinfunction "C_C") (pintype "passive"))
      (node (ref "Q4") (pin "2") (pinfunction "S_2") (pintype "passive"))
      (node (ref "R13") (pin "2") (pinfunction "2_2") (pintype "passive"))
      (node (ref "R18") (pin "P$2") (pinfunction "2_P$2") (pintype "passive"))
    )
    (net (code "20") (name "/CELL_4_BAL") (class "Default")
      (node (ref "R16") (pin "1") (pinfunction "1_1") (pintype "passive"))
      (node (ref "U$1") (pin "19") (pinfunction "S4_19") (pintype "bidirectional"))
    )
    (net (code "21") (name "/CELL_4_FILTER") (class "Default")
      (node (ref "C4") (pin "1") (pinfunction "1_1") (pintype "passive"))
      (node (ref "D7") (pin "C") (pinfunction "C_C") (pintype "passive"))
      (node (ref "D9") (pin "A") (pinfunction "A_A") (pintype "passive"))
      (node (ref "R13") (pin "1") (pinfunction "1_1") (pintype "passive"))
      (node (ref "U$1") (pin "18") (pinfunction "C4_18") (pintype "bidirectional"))
    )
    (net (code "22") (name "/CELL_5") (class "Default")
      (node (ref "CELL-IN") (pin "4") (pinfunction "S_4") (pintype "passive"))
      (node (ref "CELL-MEAS") (pin "4") (pinfunction "S_4") (pintype "passive"))
      (node (ref "D12") (pin "C") (pinfunction "C_C") (pintype "passive"))
      (node (ref "Q5") (pin "2") (pinfunction "S_2") (pintype "passive"))
      (node (ref "R17") (pin "2") (pinfunction "2_2") (pintype "passive"))
      (node (ref "R22") (pin "P$2") (pinfunction "2_P$2") (pintype "passive"))
    )
    (net (code "23") (name "/CELL_5_BAL") (class "Default")
      (node (ref "R20") (pin "1") (pinfunction "1_1") (pintype "passive"))
      (node (ref "U$1") (pin "17") (pinfunction "S5_17") (pintype "bidirectional"))
    )
    (net (code "24") (name "/CELL_5_FILTER") (class "Default")
      (node (ref "C5") (pin "1") (pinfunction "1_1") (pintype "passive"))
      (node (ref "D11") (pin "A") (pinfunction "A_A") (pintype "passive"))
      (node (ref "D9") (pin "C") (pinfunction "C_C") (pintype "passive"))
      (node (ref "R17") (pin "1") (pinfunction "1_1") (pintype "passive"))
      (node (ref "U$1") (pin "16") (pinfunction "C5_16") (pintype "bidirectional"))
    )
    (net (code "25") (name "/CELL_6") (class "Default")
      (node (ref "CELL-IN") (pin "3") (pinfunction "S_3") (pintype "passive"))
      (node (ref "CELL-MEAS") (pin "3") (pinfunction "S_3") (pintype "passive"))
      (node (ref "D14") (pin "C") (pinfunction "C_C") (pintype "passive"))
      (node (ref "Q6") (pin "2") (pinfunction "S_2") (pintype "passive"))
      (node (ref "R21") (pin "2") (pinfunction "2_2") (pintype "passive"))
      (node (ref "R26") (pin "P$2") (pinfunction "2_P$2") (pintype "passive"))
    )
    (net (code "26") (name "/CELL_6_BAL") (class "Default")
      (node (ref "R24") (pin "1") (pinfunction "1_1") (pintype "passive"))
      (node (ref "U$1") (pin "15") (pinfunction "S6_15") (pintype "bidirectional"))
    )
    (net (code "27") (name "/CELL_6_FILTER") (class "Default")
      (node (ref "C6") (pin "1") (pinfunction "1_1") (pintype "passive"))
      (node (ref "D11") (pin "C") (pinfunction "C_C") (pintype "passive"))
      (node (ref "D13") (pin "A") (pinfunction "A_A") (pintype "passive"))
      (node (ref "R21") (pin "1") (pinfunction "1_1") (pintype "passive"))
      (node (ref "U$1") (pin "14") (pinfunction "C6_14") (pintype "bidirectional"))
    )
    (net (code "28") (name "/CELL_7") (class "Default")
      (node (ref "CELL-IN") (pin "2") (pinfunction "S_2") (pintype "passive"))
      (node (ref "CELL-MEAS") (pin "2") (pinfunction "S_2") (pintype "passive"))
      (node (ref "D16") (pin "C") (pinfunction "C_C") (pintype "passive"))
      (node (ref "Q7") (pin "2") (pinfunction "S_2") (pintype "passive"))
      (node (ref "R25") (pin "2") (pinfunction "2_2") (pintype "passive"))
      (node (ref "R30") (pin "P$2") (pinfunction "2_P$2") (pintype "passive"))
    )
    (net (code "29") (name "/CELL_7_BAL") (class "Default")
      (node (ref "R28") (pin "1") (pinfunction "1_1") (pintype "passive"))
      (node (ref "U$1") (pin "13") (pinfunction "S7_13") (pintype "bidirectional"))
    )
    (net (code "30") (name "/CELL_7_FILTER") (class "Default")
      (node (ref "C7") (pin "1") (pinfunction "1_1") (pintype "passive"))
      (node (ref "D13") (pin "C") (pinfunction "C_C") (pintype "passive"))
      (node (ref "D15") (pin "A") (pinfunction "A_A") (pintype "passive"))
      (node (ref "R25") (pin "1") (pinfunction "1_1") (pintype "passive"))
      (node (ref "U$1") (pin "12") (pinfunction "C7_12") (pintype "bidirectional"))
    )
    (net (code "31") (name "/CELL_8") (class "Default")
      (node (ref "CELL-IN") (pin "1") (pinfunction "S_1") (pintype "passive"))
      (node (ref "CELL-MEAS") (pin "1") (pinfunction "S_1") (pintype "passive"))
      (node (ref "L1") (pin "1") (pinfunction "1_1") (pintype "passive"))
      (node (ref "Q8") (pin "2") (pinfunction "S_2") (pintype "passive"))
      (node (ref "R29") (pin "2") (pinfunction "2_2") (pintype "passive"))
      (node (ref "U$2") (pin "4_1") (pinfunction "IP+_4_1") (pintype "bidirectional"))
      (node (ref "U$2") (pin "4_10") (pinfunction "IP+_4_10") (pintype "bidirectional"))
      (node (ref "U$2") (pin "4_11") (pinfunction "IP+_4_11") (pintype "bidirectional"))
      (node (ref "U$2") (pin "4_12") (pinfunction "IP+_4_12") (pintype "bidirectional"))
      (node (ref "U$2") (pin "4_13") (pinfunction "IP+_4_13") (pintype "bidirectional"))
      (node (ref "U$2") (pin "4_14") (pinfunction "IP+_4_14") (pintype "bidirectional"))
      (node (ref "U$2") (pin "4_15") (pinfunction "IP+_4_15") (pintype "bidirectional"))
      (node (ref "U$2") (pin "4_16") (pinfunction "IP+_4_16") (pintype "bidirectional"))
      (node (ref "U$2") (pin "4_2") (pinfunction "IP+_4_2") (pintype "bidirectional"))
      (node (ref "U$2") (pin "4_3") (pinfunction "IP+_4_3") (pintype "bidirectional"))
      (node (ref "U$2") (pin "4_4") (pinfunction "IP+_4_4") (pintype "bidirectional"))
      (node (ref "U$2") (pin "4_5") (pinfunction "IP+_4_5") (pintype "bidirectional"))
      (node (ref "U$2") (pin "4_6") (pinfunction "IP+_4_6") (pintype "bidirectional"))
      (node (ref "U$2") (pin "4_7") (pinfunction "IP+_4_7") (pintype "bidirectional"))
      (node (ref "U$2") (pin "4_8") (pinfunction "IP+_4_8") (pintype "bidirectional"))
      (node (ref "U$2") (pin "4_9") (pinfunction "IP+_4_9") (pintype "bidirectional"))
      (node (ref "U$2") (pin "4_B") (pinfunction "IP+_4_B") (pintype "bidirectional"))
      (node (ref "U$2") (pin "4_T") (pinfunction "IP+_4_T") (pintype "bidirectional"))
      (node (ref "V_ARRAY") (pin "P$1") (pinfunction "P$1_P$1") (pintype "bidirectional"))
    )
    (net (code "32") (name "/CELL_8_BAL") (class "Default")
      (node (ref "R32") (pin "1") (pinfunction "1_1") (pintype "passive"))
      (node (ref "U$1") (pin "11") (pinfunction "S8_11") (pintype "bidirectional"))
    )
    (net (code "33") (name "/CELL_8_FILTER") (class "Default")
      (node (ref "C8") (pin "1") (pinfunction "1_1") (pintype "passive"))
      (node (ref "D15") (pin "C") (pinfunction "C_C") (pintype "passive"))
      (node (ref "R29") (pin "1") (pinfunction "1_1") (pintype "passive"))
      (node (ref "U$1") (pin "10") (pinfunction "C8_10") (pintype "bidirectional"))
      (node (ref "U$1") (pin "2") (pinfunction "C12_2") (pintype "bidirectional"))
      (node (ref "U$1") (pin "4") (pinfunction "C11_4") (pintype "bidirectional"))
      (node (ref "U$1") (pin "6") (pinfunction "C10_6") (pintype "bidirectional"))
      (node (ref "U$1") (pin "8") (pinfunction "C9_8") (pintype "bidirectional"))
    )
    (net (code "34") (name "/CHARGER+") (class "Default")
      (node (ref "J1") (pin "PIN1-1") (pinfunction "1-1_PIN1-1") (pintype "bidirectional"))
      (node (ref "J1") (pin "PIN1-2") (pinfunction "1-2_PIN1-2") (pintype "bidirectional"))
      (node (ref "JP4") (pin "4") (pinfunction "4_4") (pintype "passive"))
      (node (ref "R43") (pin "2") (pinfunction "2_2") (pintype "passive"))
      (node (ref "U$10") (pin "+") (pinfunction "+_+") (pintype "passive"))
      (node (ref "U$11") (pin "+") (pinfunction "+_+") (pintype "passive"))
      (node (ref "U$16") (pin "P$5") (pinfunction "D1_P$5") (pintype "bidirectional"))
      (node (ref "U$16") (pin "P$6") (pinfunction "D2_P$6") (pintype "bidirectional"))
      (node (ref "U$16") (pin "P$7") (pinfunction "D3_P$7") (pintype "bidirectional"))
      (node (ref "U$16") (pin "P$8") (pinfunction "D4_P$8") (pintype "bidirectional"))
      (node (ref "U$16") (pin "P$9") (pinfunction "D1_P$9") (pintype "bidirectional"))
    )
    (net (code "35") (name "/CHARGER_CTL_B") (class "Default")
      (node (ref "U$13") (pin "7.6") (pinfunction "P7.6_7.6") (pintype "bidirectional"))
      (node (ref "U$18") (pin "P$2") (pinfunction "BINP_P$2") (pintype "bidirectional"))
    )
    (net (code "36") (name "/CHARGER_CTL_T") (class "Default")
      (node (ref "U$13") (pin "8.0") (pinfunction "P8.0_8.0") (pintype "bidirectional"))
      (node (ref "U$18") (pin "P$1") (pinfunction "TINP_P$1") (pintype "bidirectional"))
    )
    (net (code "37") (name "/CHARGER_I_MEAS") (class "Default")
      (node (ref "U$13") (pin "5.2") (pinfunction "P5.2_5.2") (pintype "bidirectional"))
      (node (ref "U$4") (pin "3") (pinfunction "VIOUT_3") (pintype "bidirectional"))
    )
    (net (code "38") (name "/ESTOP_1") (class "Default")
      (node (ref "JP3") (pin "2") (pinfunction "2_2") (pintype "passive"))
      (node (ref "R45") (pin "1") (pinfunction "1_1") (pintype "passive"))
      (node (ref "U$13") (pin "1.5") (pinfunction "P1.5_1.5") (pintype "bidirectional"))
    )
    (net (code "39") (name "/ESTOP_2") (class "Default")
      (node (ref "JP2") (pin "2") (pinfunction "2_2") (pintype "passive"))
      (node (ref "R46") (pin "1") (pinfunction "1_1") (pintype "passive"))
      (node (ref "U$13") (pin "1.6") (pinfunction "P1.6_1.6") (pintype "bidirectional"))
    )
    (net (code "40") (name "/FAN_CTL_1") (class "Default")
      (node (ref "Q12") (pin "1") (pinfunction "G_1") (pintype "passive"))
      (node (ref "U$13") (pin "2.4") (pinfunction "P2.4_2.4") (pintype "bidirectional"))
    )
    (net (code "41") (name "/FAN_CTL_2") (class "Default")
      (node (ref "Q13") (pin "1") (pinfunction "G_1") (pintype "passive"))
      (node (ref "U$13") (pin "2.5") (pinfunction "P2.5_2.5") (pintype "bidirectional"))
    )
    (net (code "42") (name "/FAN_CTL_3") (class "Default")
      (node (ref "Q14") (pin "1") (pinfunction "G_1") (pintype "passive"))
      (node (ref "U$13") (pin "2.6") (pinfunction "P2.6_2.6") (pintype "bidirectional"))
    )
    (net (code "43") (name "/FAN_CTL_4") (class "Default")
      (node (ref "Q15") (pin "1") (pinfunction "G_1") (pintype "passive"))
      (node (ref "U$13") (pin "2.7") (pinfunction "P2.7_2.7") (pintype "bidirectional"))
    )
    (net (code "44") (name "/FAN_TACH_1") (class "Default")
      (node (ref "U$13") (pin "5.0") (pinfunction "P5.0_5.0") (pintype "bidirectional"))
      (node (ref "X1") (pin "3") (pinfunction "S_3") (pintype "passive"))
    )
    (net (code "45") (name "/FAN_TACH_2") (class "Default")
      (node (ref "U$13") (pin "3.3") (pinfunction "P3.3_3.3") (pintype "bidirectional"))
      (node (ref "X2") (pin "3") (pinfunction "S_3") (pintype "passive"))
    )
    (net (code "46") (name "/FAN_TACH_3") (class "Default")
      (node (ref "U$13") (pin "3.2") (pinfunction "P3.2_3.2") (pintype "bidirectional"))
      (node (ref "X3") (pin "3") (pinfunction "S_3") (pintype "passive"))
    )
    (net (code "47") (name "/FAN_TACH_4") (class "Default")
      (node (ref "U$13") (pin "3.0") (pinfunction "P3.0_3.0") (pintype "bidirectional"))
      (node (ref "X4") (pin "3") (pinfunction "S_3") (pintype "passive"))
    )
    (net (code "48") (name "/GAUGE_ON") (class "Default")
      (node (ref "GAUGE_ON") (pin "2") (pinfunction "2_2") (pintype "passive"))
      (node (ref "IC2") (pin "P$10") (pinfunction "/G_P$10") (pintype "bidirectional"))
      (node (ref "R57") (pin "2") (pinfunction "2_2") (pintype "passive"))
      (node (ref "S2") (pin "3") (pinfunction "2_3") (pintype "passive"))
      (node (ref "U$13") (pin "6.6") (pinfunction "P6.6_6.6") (pintype "bidirectional"))
    )
    (net (code "49") (name "/LCD_DB[0]") (class "Default")
      (node (ref "JP5") (pin "7") (pinfunction "7_7") (pintype "passive"))
      (node (ref "U$13") (pin "4.0") (pinfunction "P4.0_4.0") (pintype "bidirectional"))
    )
    (net (code "50") (name "/LCD_DB[1]") (class "Default")
      (node (ref "JP5") (pin "8") (pinfunction "8_8") (pintype "passive"))
      (node (ref "U$13") (pin "4.1") (pinfunction "P4.1_4.1") (pintype "bidirectional"))
    )
    (net (code "51") (name "/LCD_DB[2]") (class "Default")
      (node (ref "JP5") (pin "9") (pinfunction "9_9") (pintype "passive"))
      (node (ref "U$13") (pin "4.2") (pinfunction "P4.2_4.2") (pintype "bidirectional"))
    )
    (net (code "52") (name "/LCD_DB[3]") (class "Default")
      (node (ref "JP5") (pin "10") (pinfunction "10_10") (pintype "passive"))
      (node (ref "U$13") (pin "4.3") (pinfunction "P4.3_4.3") (pintype "bidirectional"))
    )
    (net (code "53") (name "/LCD_DB[4]") (class "Default")
      (node (ref "JP5") (pin "11") (pinfunction "11_11") (pintype "passive"))
      (node (ref "U$13") (pin "4.4") (pinfunction "P4.4_4.4") (pintype "bidirectional"))
    )
    (net (code "54") (name "/LCD_DB[5]") (class "Default")
      (node (ref "JP5") (pin "12") (pinfunction "12_12") (pintype "passive"))
      (node (ref "U$13") (pin "4.5") (pinfunction "P4.5_4.5") (pintype "bidirectional"))
    )
    (net (code "55") (name "/LCD_DB[6]") (class "Default")
      (node (ref "JP5") (pin "13") (pinfunction "13_13") (pintype "passive"))
      (node (ref "U$13") (pin "4.6") (pinfunction "P4.6_4.6") (pintype "bidirectional"))
    )
    (net (code "56") (name "/LCD_DB[7]") (class "Default")
      (node (ref "JP5") (pin "14") (pinfunction "14_14") (pintype "passive"))
      (node (ref "U$13") (pin "4.7") (pinfunction "P4.7_4.7") (pintype "bidirectional"))
    )
    (net (code "57") (name "/LCD_EN") (class "Default")
      (node (ref "JP5") (pin "6") (pinfunction "6_6") (pintype "passive"))
      (node (ref "U$13") (pin "3.7") (pinfunction "P3.7_3.7") (pintype "bidirectional"))
    )
    (net (code "58") (name "/LCD_RS") (class "Default")
      (node (ref "JP5") (pin "4") (pinfunction "4_4") (pintype "passive"))
      (node (ref "U$13") (pin "3.5") (pinfunction "P3.5_3.5") (pintype "bidirectional"))
    )
    (net (code "59") (name "/LCD_RW") (class "Default")
      (node (ref "JP5") (pin "5") (pinfunction "5_5") (pintype "passive"))
      (node (ref "U$13") (pin "3.6") (pinfunction "P3.6_3.6") (pintype "bidirectional"))
    )
    (net (code "60") (name "/LCD_VBACK") (class "Default")
      (node (ref "JP5") (pin "3") (pinfunction "3_3") (pintype "passive"))
      (node (ref "RV1") (pin "1") (pinfunction "S_1") (pintype "passive"))
    )
    (net (code "61") (name "/LED_CLR") (class "Default")
      (node (ref "IC2") (pin "P$9") (pinfunction "/CLR_P$9") (pintype "bidirectional"))
      (node (ref "U$13") (pin "10.0") (pinfunction "P10.0_10.0") (pintype "bidirectional"))
    )
    (net (code "62") (name "/LED_RCK") (class "Default")
      (node (ref "IC2") (pin "P$12") (pinfunction "RCK_P$12") (pintype "bidirectional"))
      (node (ref "U$13") (pin "10.1") (pinfunction "P10.1_10.1") (pintype "bidirectional"))
    )
    (net (code "63") (name "/LED_SER_IN") (class "Default")
      (node (ref "IC2") (pin "P$2") (pinfunction "SER_IN_P$2") (pintype "bidirectional"))
      (node (ref "U$13") (pin "10.2") (pinfunction "P10.2_10.2") (pintype "bidirectional"))
    )
    (net (code "64") (name "/LED_SRCK") (class "Default")
      (node (ref "IC2") (pin "P$19") (pinfunction "SRCK_P$19") (pintype "bidirectional"))
      (node (ref "U$13") (pin "10.3") (pinfunction "P10.3_10.3") (pintype "bidirectional"))
    )
    (net (code "65") (name "/LOGIC_POWER") (class "Default")
      (node (ref "C17") (pin "+") (pinfunction "+_+") (pintype "passive"))
      (node (ref "C18") (pin "+") (pinfunction "+_+") (pintype "passive"))
      (node (ref "F1") (pin "P$2") (pinfunction "P$2_P$2") (pintype "bidirectional"))
      (node (ref "OKI-78SR") (pin "1") (pinfunction "VI_1") (pintype "bidirectional"))
      (node (ref "OKI-78SR1") (pin "1") (pinfunction "VI_1") (pintype "bidirectional"))
    )
    (net (code "66") (name "/N$115") (class "Default")
      (node (ref "JP5") (pin "15") (pinfunction "15_15") (pintype "passive"))
    )
    (net (code "67") (name "/N$116") (class "Default")
      (node (ref "JP5") (pin "16") (pinfunction "16_16") (pintype "passive"))
    )
    (net (code "68") (name "/PACK_GATE") (class "Default")
      (node (ref "U$13") (pin "6.0") (pinfunction "P6.0_6.0") (pintype "bidirectional"))
      (node (ref "U$8") (pin "4") (pinfunction "IN_4") (pintype "bidirectional"))
    )
    (net (code "69") (name "/PACK_I_MEAS") (class "Default")
      (node (ref "U$13") (pin "5.5") (pinfunction "P5.5_5.5") (pintype "bidirectional"))
      (node (ref "U$2") (pin "3") (pinfunction "VIOUT_3") (pintype "bidirectional"))
    )
    (net (code "70") (name "/SER_IN") (class "Default")
      (node (ref "U$13") (pin "9.6") (pinfunction "P9.6_9.6") (pintype "bidirectional"))
      (node (ref "U$15") (pin "RO") (pinfunction "R0_RO") (pintype "bidirectional"))
    )
    (net (code "71") (name "/SER_OUT") (class "Default")
      (node (ref "U$13") (pin "9.7") (pinfunction "P9.7_9.7") (pintype "bidirectional"))
      (node (ref "U$15") (pin "DI") (pinfunction "DI_DI") (pintype "bidirectional"))
    )
    (net (code "72") (name "/SUPPLY_CTL") (class "Default")
      (node (ref "JP4") (pin "6") (pinfunction "6_6") (pintype "passive"))
      (node (ref "U$13") (pin "2.3") (pinfunction "P2.3_2.3") (pintype "bidirectional"))
    )
    (net (code "73") (name "/SUPPLY_DC_OK") (class "Default")
      (node (ref "JP4") (pin "1") (pinfunction "1_1") (pintype "passive"))
      (node (ref "U$13") (pin "1.7") (pinfunction "P1.7_1.7") (pintype "bidirectional"))
    )
    (net (code "74") (name "/TEMP_1") (class "Default")
      (node (ref "C11") (pin "1") (pinfunction "1_1") (pintype "passive"))
      (node (ref "R34") (pin "1") (pinfunction "1_1") (pintype "passive"))
      (node (ref "U$1") (pin "28") (pinfunction "VTEMP1_28") (pintype "bidirectional"))
    )
    (net (code "75") (name "/TEMP_2") (class "Default")
      (node (ref "C12") (pin "1") (pinfunction "1_1") (pintype "passive"))
      (node (ref "R36") (pin "1") (pinfunction "1_1") (pintype "passive"))
      (node (ref "U$1") (pin "29") (pinfunction "VTEMP2_29") (pintype "bidirectional"))
    )
    (net (code "76") (name "/V_CHECK_ARRAY") (class "Default")
      (node (ref "R41") (pin "1") (pinfunction "1_1") (pintype "passive"))
      (node (ref "R42") (pin "2") (pinfunction "2_2") (pintype "passive"))
      (node (ref "U$13") (pin "5.3") (pinfunction "P5.3_5.3") (pintype "bidirectional"))
    )
    (net (code "77") (name "/V_CHECK_CHARGER_IN") (class "Default")
      (node (ref "R43") (pin "1") (pinfunction "1_1") (pintype "passive"))
      (node (ref "R44") (pin "2") (pinfunction "2_2") (pintype "passive"))
      (node (ref "U$13") (pin "5.1") (pinfunction "P5.1_5.1") (pintype "bidirectional"))
    )
    (net (code "78") (name "/V_CHECK_OUT") (class "Default")
      (node (ref "R38") (pin "2") (pinfunction "2_2") (pintype "passive"))
      (node (ref "R39") (pin "1") (pinfunction "1_1") (pintype "passive"))
      (node (ref "U$13") (pin "5.4") (pinfunction "P5.4_5.4") (pintype "bidirectional"))
    )
    (net (code "79") (name "5V") (class "Default")
      (node (ref "BUZZER_1") (pin "+") (pinfunction "1_+") (pintype "passive"))
      (node (ref "BUZZER_2") (pin "-") (pinfunction "2_-") (pintype "passive"))
      (node (ref "C21") (pin "1") (pinfunction "1_1") (pintype "passive"))
      (node (ref "C22") (pin "1") (pinfunction "1_1") (pintype "passive"))
      (node (ref "C23") (pin "+") (pinfunction "+_+") (pintype "passive"))
      (node (ref "IC2") (pin "P$1") (pinfunction "VCC_P$1") (pintype "bidirectional"))
      (node (ref "JP5") (pin "2") (pinfunction "2_2") (pintype "passive"))
      (node (ref "OKI-78SR") (pin "3") (pinfunction "VO_3") (pintype "bidirectional"))
      (node (ref "R45") (pin "2") (pinfunction "2_2") (pintype "passive"))
      (node (ref "R46") (pin "2") (pinfunction "2_2") (pintype "passive"))
      (node (ref "R47") (pin "2") (pinfunction "2_2") (pintype "passive"))
      (node (ref "R48") (pin "2") (pinfunction "2_2") (pintype "passive"))
      (node (ref "R49") (pin "2") (pinfunction "2_2") (pintype "passive"))
      (node (ref "R50") (pin "2") (pinfunction "2_2") (pintype "passive"))
      (node (ref "R51") (pin "2") (pinfunction "2_2") (pintype "passive"))
      (node (ref "R52") (pin "2") (pinfunction "2_2") (pintype "passive"))
      (node (ref "R53") (pin "2") (pinfunction "2_2") (pintype "passive"))
      (node (ref "R54") (pin "2") (pinfunction "2_2") (pintype "passive"))
      (node (ref "R55") (pin "2") (pinfunction "2_2") (pintype "passive"))
      (node (ref "R56") (pin "2") (pinfunction "2_2") (pintype "passive"))
      (node (ref "R57") (pin "1") (pinfunction "1_1") (pintype "passive"))
      (node (ref "R58") (pin "1") (pinfunction "1_1") (pintype "passive"))
      (node (ref "R59") (pin "1") (pinfunction "1_1") (pintype "passive"))
      (node (ref "R60") (pin "1") (pinfunction "1_1") (pintype "passive"))
      (node (ref "R61") (pin "1") (pinfunction "1_1") (pintype "passive"))
      (node (ref "R62") (pin "1") (pinfunction "1_1") (pintype "passive"))
      (node (ref "R63") (pin "1") (pinfunction "1_1") (pintype "passive"))
      (node (ref "R64") (pin "1") (pinfunction "1_1") (pintype "passive"))
      (node (ref "R65") (pin "1") (pinfunction "1_1") (pintype "passive"))
      (node (ref "R66") (pin "1") (pinfunction "1_1") (pintype "passive"))
      (node (ref "R67") (pin "1") (pinfunction "1_1") (pintype "passive"))
      (node (ref "RV1") (pin "3") (pinfunction "A_3") (pintype "passive"))
      (node (ref "U$13") (pin "5V_1") (pinfunction "5V_1_5V_1") (pintype "bidirectional"))
      (node (ref "U$13") (pin "5V_2") (pinfunction "5V_2_5V_2") (pintype "bidirectional"))
      (node (ref "U$13") (pin "5V_3") (pinfunction "5V_3_5V_3") (pintype "bidirectional"))
      (node (ref "U$13") (pin "5V_4") (pinfunction "5V_4_5V_4") (pintype "bidirectional"))
      (node (ref "U$15") (pin "VCC") (pinfunction "VCC_VCC") (pintype "bidirectional"))
      (node (ref "U$2") (pin "1") (pinfunction "VCC_1") (pintype "bidirectional"))
      (node (ref "U$4") (pin "1") (pinfunction "VCC_1") (pintype "bidirectional"))
    )
    (net (code "80") (name "GND") (class "Default")
      (node (ref "C1") (pin "2") (pinfunction "2_2") (pintype "passive"))
      (node (ref "C10") (pin "2") (pinfunction "2_2") (pintype "passive"))
      (node (ref "C11") (pin "2") (pinfunction "2_2") (pintype "passive"))
      (node (ref "C12") (pin "2") (pinfunction "2_2") (pintype "passive"))
      (node (ref "C13") (pin "2") (pinfunction "2_2") (pintype "passive"))
      (node (ref "C14") (pin "2") (pinfunction "2_2") (pintype "passive"))
      (node (ref "C16") (pin "2") (pinfunction "2_2") (pintype "passive"))
      (node (ref "C17") (pin "-") (pinfunction "-_-") (pintype "passive"))
      (node (ref "C18") (pin "-") (pinfunction "-_-") (pintype "passive"))
      (node (ref "C2") (pin "2") (pinfunction "2_2") (pintype "passive"))
      (node (ref "C21") (pin "2") (pinfunction "2_2") (pintype "passive"))
      (node (ref "C22") (pin "2") (pinfunction "2_2") (pintype "passive"))
      (node (ref "C23") (pin "-") (pinfunction "-_-") (pintype "passive"))
      (node (ref "C24") (pin "-") (pinfunction "-_-") (pintype "passive"))
      (node (ref "C3") (pin "2") (pinfunction "2_2") (pintype "passive"))
      (node (ref "C4") (pin "2") (pinfunction "2_2") (pintype "passive"))
      (node (ref "C5") (pin "2") (pinfunction "2_2") (pintype "passive"))
      (node (ref "C6") (pin "2") (pinfunction "2_2") (pintype "passive"))
      (node (ref "C7") (pin "2") (pinfunction "2_2") (pintype "passive"))
      (node (ref "C8") (pin "2") (pinfunction "2_2") (pintype "passive"))
      (node (ref "C9") (pin "2") (pinfunction "2_2") (pintype "passive"))
      (node (ref "CELL-IN") (pin "9") (pinfunction "S_9") (pintype "passive"))
      (node (ref "CELL-MEAS") (pin "9") (pinfunction "S_9") (pintype "passive"))
      (node (ref "D1") (pin "A") (pinfunction "A_A") (pintype "passive"))
      (node (ref "D17") (pin "A") (pinfunction "A_A") (pintype "passive"))
      (node (ref "D18") (pin "A") (pinfunction "A_A") (pintype "passive"))
      (node (ref "D19") (pin "A") (pinfunction "A_A") (pintype "passive"))
      (node (ref "D2") (pin "C") (pinfunction "C_C") (pintype "passive"))
      (node (ref "GAUGE_ON") (pin "1") (pinfunction "1_1") (pintype "passive"))
      (node (ref "IC1") (pin "4") (pinfunction "V-_4") (pintype "power_in"))
      (node (ref "IC2") (pin "P$20") (pinfunction "GND_P$20") (pintype "bidirectional"))
      (node (ref "J1") (pin "PIN2-1") (pinfunction "2-1_PIN2-1") (pintype "bidirectional"))
      (node (ref "J1") (pin "PIN2-2") (pinfunction "2-2_PIN2-2") (pintype "bidirectional"))
      (node (ref "JP2") (pin "1") (pinfunction "1_1") (pintype "passive"))
      (node (ref "JP3") (pin "1") (pinfunction "1_1") (pintype "passive"))
      (node (ref "JP4") (pin "2") (pinfunction "2_2") (pintype "passive"))
      (node (ref "JP4") (pin "3") (pinfunction "3_3") (pintype "passive"))
      (node (ref "JP4") (pin "5") (pinfunction "5_5") (pintype "passive"))
      (node (ref "JP5") (pin "1") (pinfunction "1_1") (pintype "passive"))
      (node (ref "OKI-78SR") (pin "2") (pinfunction "GND_2") (pintype "bidirectional"))
      (node (ref "OKI-78SR1") (pin "2") (pinfunction "GND_2") (pintype "bidirectional"))
      (node (ref "Q10") (pin "2") (pinfunction "S_2") (pintype "passive"))
      (node (ref "Q11") (pin "2") (pinfunction "S_2") (pintype "passive"))
      (node (ref "Q12") (pin "2") (pinfunction "S_2") (pintype "passive"))
      (node (ref "Q13") (pin "2") (pinfunction "S_2") (pintype "passive"))
      (node (ref "Q14") (pin "2") (pinfunction "S_2") (pintype "passive"))
      (node (ref "Q15") (pin "2") (pinfunction "S_2") (pintype "passive"))
      (node (ref "R2") (pin "P$2") (pinfunction "2_P$2") (pintype "passive"))
      (node (ref "R39") (pin "2") (pinfunction "2_2") (pintype "passive"))
      (node (ref "R40") (pin "2") (pinfunction "2_2") (pintype "passive"))
      (node (ref "R42") (pin "1") (pinfunction "1_1") (pintype "passive"))
      (node (ref "R44") (pin "1") (pinfunction "1_1") (pintype "passive"))
      (node (ref "RV1") (pin "2") (pinfunction "E_2") (pintype "passive"))
      (node (ref "S1") (pin "3") (pinfunction "S_3") (pintype "passive"))
      (node (ref "S2") (pin "1") (pinfunction "1_1") (pintype "passive"))
      (node (ref "THERM_1") (pin "2") (pinfunction "S_2") (pintype "passive"))
      (node (ref "THERM_2") (pin "2") (pinfunction "S_2") (pintype "passive"))
      (node (ref "U$1") (pin "26") (pinfunction "V-_26") (pintype "bidirectional"))
      (node (ref "U$1") (pin "32") (pinfunction "TOS_32") (pintype "bidirectional"))
      (node (ref "U$1") (pin "35") (pinfunction "GPIO1_35") (pintype "bidirectional"))
      (node (ref "U$1") (pin "36") (pinfunction "GPIO2_36") (pintype "bidirectional"))
      (node (ref "U$1") (pin "37") (pinfunction "A0_37") (pintype "bidirectional"))
      (node (ref "U$1") (pin "38") (pinfunction "A1_38") (pintype "bidirectional"))
      (node (ref "U$1") (pin "39") (pinfunction "A2_39") (pintype "bidirectional"))
      (node (ref "U$1") (pin "40") (pinfunction "A3_40") (pintype "bidirectional"))
      (node (ref "U$10") (pin "GND") (pinfunction "-_GND") (pintype "passive"))
      (node (ref "U$11") (pin "GND") (pinfunction "-_GND") (pintype "passive"))
      (node (ref "U$13") (pin "GND_1") (pinfunction "GND1_GND_1") (pintype "bidirectional"))
      (node (ref "U$13") (pin "GND_2") (pinfunction "GND2_GND_2") (pintype "bidirectional"))
      (node (ref "U$13") (pin "GND_3") (pinfunction "GND3_GND_3") (pintype "bidirectional"))
      (node (ref "U$13") (pin "GND_4") (pinfunction "GND4_GND_4") (pintype "bidirectional"))
      (node (ref "U$13") (pin "GND_5") (pinfunction "GND5_GND_5") (pintype "bidirectional"))
      (node (ref "U$13") (pin "GND_6") (pinfunction "GND6_GND_6") (pintype "bidirectional"))
      (node (ref "U$13") (pin "GND_7") (pinfunction "GND7_GND_7") (pintype "bidirectional"))
      (node (ref "U$13") (pin "GND_8") (pinfunction "GND8_GND_8") (pintype "bidirectional"))
      (node (ref "U$14") (pin "7") (pinfunction "7_7") (pintype "bidirectional"))
      (node (ref "U$14") (pin "8") (pinfunction "8_8") (pintype "bidirectional"))
      (node (ref "U$15") (pin "GND") (pinfunction "GND_GND") (pintype "bidirectional"))
      (node (ref "U$17") (pin "P$1") (pinfunction "S1_P$1") (pintype "bidirectional"))
      (node (ref "U$17") (pin "P$2") (pinfunction "S2_P$2") (pintype "bidirectional"))
      (node (ref "U$17") (pin "P$3") (pinfunction "S3_P$3") (pintype "bidirectional"))
      (node (ref "U$18") (pin "P$9") (pinfunction "GND_P$9") (pintype "bidirectional"))
      (node (ref "U$2") (pin "2") (pinfunction "GND_2") (pintype "bidirectional"))
      (node (ref "U$3") (pin "GND") (pinfunction "-_GND") (pintype "passive"))
      (node (ref "U$4") (pin "2") (pinfunction "GND_2") (pintype "bidirectional"))
      (node (ref "U$6") (pin "GND") (pinfunction "-_GND") (pintype "passive"))
      (node (ref "U$7") (pin "GND") (pinfunction "-_GND") (pintype "passive"))
      (node (ref "U$8") (pin "1") (pinfunction "GND_1") (pintype "bidirectional"))
      (node (ref "U$9") (pin "P$1") (pinfunction "A_P$1") (pintype "passive"))
      (node (ref "U$9") (pin "P$3") (pinfunction "A_P$3") (pintype "passive"))
      (node (ref "V_OUT1") (pin "P$1") (pinfunction "P$1_P$1") (pintype "bidirectional"))
    )
    (net (code "81") (name "Net-(BUZZER_1-2)") (class "Default")
      (node (ref "BUZZER_1") (pin "-") (pinfunction "2_-") (pintype "passive"))
      (node (ref "Q11") (pin "3") (pinfunction "D_3") (pintype "passive"))
    )
    (net (code "82") (name "Net-(BUZZER_2-1)") (class "Default")
      (node (ref "BUZZER_2") (pin "+") (pinfunction "1_+") (pintype "passive"))
      (node (ref "Q10") (pin "3") (pinfunction "D_3") (pintype "passive"))
    )
    (net (code "83") (name "Net-(D2-PadA)") (class "Default")
      (node (ref "D2") (pin "A") (pinfunction "A_A") (pintype "passive"))
      (node (ref "R3") (pin "2") (pinfunction "2_2") (pintype "passive"))
    )
    (net (code "84") (name "Net-(D4-PadA)") (class "Default")
      (node (ref "D4") (pin "A") (pinfunction "A_A") (pintype "passive"))
      (node (ref "R7") (pin "2") (pinfunction "2_2") (pintype "passive"))
    )
    (net (code "85") (name "Net-(D6-PadA)") (class "Default")
      (node (ref "D6") (pin "A") (pinfunction "A_A") (pintype "passive"))
      (node (ref "R11") (pin "2") (pinfunction "2_2") (pintype "passive"))
    )
    (net (code "86") (name "Net-(D8-PadA)") (class "Default")
      (node (ref "D8") (pin "A") (pinfunction "A_A") (pintype "passive"))
      (node (ref "R15") (pin "2") (pinfunction "2_2") (pintype "passive"))
    )
    (net (code "87") (name "Net-(D10-PadA)") (class "Default")
      (node (ref "D10") (pin "A") (pinfunction "A_A") (pintype "passive"))
      (node (ref "R19") (pin "2") (pinfunction "2_2") (pintype "passive"))
    )
    (net (code "88") (name "Net-(D12-PadA)") (class "Default")
      (node (ref "D12") (pin "A") (pinfunction "A_A") (pintype "passive"))
      (node (ref "R23") (pin "2") (pinfunction "2_2") (pintype "passive"))
    )
    (net (code "89") (name "Net-(D14-PadA)") (class "Default")
      (node (ref "D14") (pin "A") (pinfunction "A_A") (pintype "passive"))
      (node (ref "R27") (pin "2") (pinfunction "2_2") (pintype "passive"))
    )
    (net (code "90") (name "Net-(D16-PadA)") (class "Default")
      (node (ref "D16") (pin "A") (pinfunction "A_A") (pintype "passive"))
      (node (ref "R31") (pin "2") (pinfunction "2_2") (pintype "passive"))
    )
    (net (code "91") (name "Net-(D17-PadC)") (class "Default")
      (node (ref "D17") (pin "C") (pinfunction "C_C") (pintype "passive"))
      (node (ref "D18") (pin "C") (pinfunction "C_C") (pintype "passive"))
      (node (ref "D19") (pin "C") (pinfunction "C_C") (pintype "passive"))
      (node (ref "L1") (pin "2") (pinfunction "2_2") (pintype "passive"))
      (node (ref "R37") (pin "2") (pinfunction "2_2") (pintype "passive"))
    )
    (net (code "92") (name "Net-(D20-C)") (class "Default")
      (node (ref "C15") (pin "1") (pinfunction "1_1") (pintype "passive"))
      (node (ref "D20") (pin "3") (pinfunction "C_3") (pintype "passive"))
      (node (ref "U$18") (pin "P$6") (pinfunction "BOOST_P$6") (pintype "bidirectional"))
    )
    (net (code "93") (name "Net-(GAGUE_S-Pad1)") (class "Default")
      (node (ref "GAGUE_S") (pin "1") (pinfunction "1_1") (pintype "passive"))
      (node (ref "R58") (pin "2") (pinfunction "2_2") (pintype "passive"))
    )
    (net (code "94") (name "Net-(GAGUE_S-Pad2)") (class "Default")
      (node (ref "GAGUE_S") (pin "2") (pinfunction "2_2") (pintype "passive"))
      (node (ref "R59") (pin "2") (pinfunction "2_2") (pintype "passive"))
    )
    (net (code "95") (name "Net-(GAGUE_S-Pad3)") (class "Default")
      (node (ref "GAGUE_S") (pin "3") (pinfunction "3_3") (pintype "passive"))
      (node (ref "R60") (pin "2") (pinfunction "2_2") (pintype "passive"))
    )
    (net (code "96") (name "Net-(GAGUE_S-Pad4)") (class "Default")
      (node (ref "GAGUE_S") (pin "4") (pinfunction "4_4") (pintype "passive"))
      (node (ref "R61") (pin "2") (pinfunction "2_2") (pintype "passive"))
    )
    (net (code "97") (name "Net-(GAGUE_S-Pad5)") (class "Default")
      (node (ref "GAGUE_S") (pin "5") (pinfunction "5_5") (pintype "passive"))
      (node (ref "R62") (pin "2") (pinfunction "2_2") (pintype "passive"))
    )
    (net (code "98") (name "Net-(GAGUE_S-Pad6)") (class "Default")
      (node (ref "GAGUE_S") (pin "6") (pinfunction "6_6") (pintype "passive"))
      (node (ref "R63") (pin "2") (pinfunction "2_2") (pintype "passive"))
    )
    (net (code "99") (name "Net-(GAGUE_S-Pad7)") (class "Default")
      (node (ref "GAGUE_S") (pin "7") (pinfunction "7_7") (pintype "passive"))
      (node (ref "R64") (pin "2") (pinfunction "2_2") (pintype "passive"))
    )
    (net (code "100") (name "Net-(GAGUE_S-Pad8)") (class "Default")
      (node (ref "GAGUE_S") (pin "8") (pinfunction "8_8") (pintype "passive"))
      (node (ref "R65") (pin "2") (pinfunction "2_2") (pintype "passive"))
    )
    (net (code "101") (name "Net-(GAGUE_S-Pad9)") (class "Default")
      (node (ref "GAGUE_S") (pin "9") (pinfunction "9_9") (pintype "passive"))
      (node (ref "R66") (pin "2") (pinfunction "2_2") (pintype "passive"))
    )
    (net (code "102") (name "Net-(GAGUE_S-Pad10)") (class "Default")
      (node (ref "GAGUE_S") (pin "10") (pinfunction "10_10") (pintype "passive"))
      (node (ref "R67") (pin "2") (pinfunction "2_2") (pintype "passive"))
    )
    (net (code "103") (name "Net-(IC1A--IN)") (class "Default")
      (node (ref "IC1") (pin "1") (pinfunction "OUT_1") (pintype "output"))
      (node (ref "IC1") (pin "2") (pinfunction "-IN_2") (pintype "input"))
      (node (ref "R33") (pin "1") (pinfunction "1_1") (pintype "passive"))
    )
    (net (code "104") (name "Net-(IC1B--IN)") (class "Default")
      (node (ref "IC1") (pin "6") (pinfunction "-IN_6") (pintype "input"))
      (node (ref "IC1") (pin "7") (pinfunction "OUT_7") (pintype "output"))
      (node (ref "R35") (pin "1") (pinfunction "1_1") (pintype "passive"))
    )
    (net (code "105") (name "Net-(IC2-DRAIN0)") (class "Default")
      (node (ref "IC2") (pin "P$3") (pinfunction "DRAIN0_P$3") (pintype "bidirectional"))
      (node (ref "JP1") (pin "10") (pinfunction "10_10") (pintype "passive"))
      (node (ref "LED2") (pin "P$20") (pinfunction "20_P$20") (pintype "bidirectional"))
    )
    (net (code "106") (name "Net-(IC2-DRAIN1)") (class "Default")
      (node (ref "IC2") (pin "P$4") (pinfunction "DRAIN1_P$4") (pintype "bidirectional"))
      (node (ref "JP1") (pin "9") (pinfunction "9_9") (pintype "passive"))
      (node (ref "LED2") (pin "P$19") (pinfunction "19_P$19") (pintype "bidirectional"))
    )
    (net (code "107") (name "Net-(IC2-DRAIN2)") (class "Default")
      (node (ref "IC2") (pin "P$5") (pinfunction "DRAIN2_P$5") (pintype "bidirectional"))
      (node (ref "JP1") (pin "8") (pinfunction "8_8") (pintype "passive"))
      (node (ref "LED2") (pin "P$18") (pinfunction "18_P$18") (pintype "bidirectional"))
    )
    (net (code "108") (name "Net-(IC2-DRAIN3)") (class "Default")
      (node (ref "IC2") (pin "P$6") (pinfunction "DRAIN3_P$6") (pintype "bidirectional"))
      (node (ref "JP1") (pin "7") (pinfunction "7_7") (pintype "passive"))
      (node (ref "LED2") (pin "P$17") (pinfunction "17_P$17") (pintype "bidirectional"))
    )
    (net (code "109") (name "Net-(IC2-DRAIN4)") (class "Default")
      (node (ref "IC2") (pin "P$7") (pinfunction "DRAIN4_P$7") (pintype "bidirectional"))
      (node (ref "JP1") (pin "6") (pinfunction "6_6") (pintype "passive"))
      (node (ref "LED2") (pin "P$16") (pinfunction "16_P$16") (pintype "bidirectional"))
    )
    (net (code "110") (name "Net-(IC2-DRAIN5)") (class "Default")
      (node (ref "IC2") (pin "P$8") (pinfunction "DRAIN5_P$8") (pintype "bidirectional"))
      (node (ref "JP1") (pin "5") (pinfunction "5_5") (pintype "passive"))
      (node (ref "LED2") (pin "P$15") (pinfunction "15_P$15") (pintype "bidirectional"))
    )
    (net (code "111") (name "Net-(IC2-DRAIN6)") (class "Default")
      (node (ref "IC2") (pin "P$13") (pinfunction "DRAIN6_P$13") (pintype "bidirectional"))
      (node (ref "JP1") (pin "4") (pinfunction "4_4") (pintype "passive"))
      (node (ref "LED2") (pin "P$14") (pinfunction "14_P$14") (pintype "bidirectional"))
    )
    (net (code "112") (name "Net-(IC2-DRAIN7)") (class "Default")
      (node (ref "IC2") (pin "P$14") (pinfunction "DRAIN7_P$14") (pintype "bidirectional"))
      (node (ref "JP1") (pin "3") (pinfunction "3_3") (pintype "passive"))
      (node (ref "LED2") (pin "P$13") (pinfunction "13_P$13") (pintype "bidirectional"))
    )
    (net (code "113") (name "Net-(IC2-DRAIN8)") (class "Default")
      (node (ref "IC2") (pin "P$15") (pinfunction "DRAIN8_P$15") (pintype "bidirectional"))
      (node (ref "JP1") (pin "2") (pinfunction "2_2") (pintype "passive"))
      (node (ref "LED2") (pin "P$12") (pinfunction "12_P$12") (pintype "bidirectional"))
    )
    (net (code "114") (name "Net-(IC2-DRAIN9)") (class "Default")
      (node (ref "IC2") (pin "P$16") (pinfunction "DRAIN9_P$16") (pintype "bidirectional"))
      (node (ref "JP1") (pin "1") (pinfunction "1_1") (pintype "passive"))
      (node (ref "LED2") (pin "P$11") (pinfunction "11_P$11") (pintype "bidirectional"))
    )
    (net (code "115") (name "Net-(IRLS3034-7P-DRAIN)") (class "Default")
      (node (ref "C14") (pin "1") (pinfunction "1_1") (pintype "passive"))
      (node (ref "IRLS3034-7P") (pin "PAD") (pinfunction "DRAIN_PAD") (pintype "bidirectional"))
      (node (ref "IRLS3034-7P.2") (pin "PAD") (pinfunction "DRAIN_PAD") (pintype "bidirectional"))
      (node (ref "R41") (pin "2") (pinfunction "2_2") (pintype "passive"))
      (node (ref "S1") (pin "1") (pinfunction "O_1") (pintype "passive"))
      (node (ref "U$2") (pin "5_1") (pinfunction "IP-_5_1") (pintype "bidirectional"))
      (node (ref "U$2") (pin "5_10") (pinfunction "IP-_5_10") (pintype "bidirectional"))
      (node (ref "U$2") (pin "5_11") (pinfunction "IP-_5_11") (pintype "bidirectional"))
      (node (ref "U$2") (pin "5_12") (pinfunction "IP-_5_12") (pintype "bidirectional"))
      (node (ref "U$2") (pin "5_13") (pinfunction "IP-_5_13") (pintype "bidirectional"))
      (node (ref "U$2") (pin "5_14") (pinfunction "IP-_5_14") (pintype "bidirectional"))
      (node (ref "U$2") (pin "5_15") (pinfunction "IP-_5_15") (pintype "bidirectional"))
      (node (ref "U$2") (pin "5_16") (pinfunction "IP-_5_16") (pintype "bidirectional"))
      (node (ref "U$2") (pin "5_2") (pinfunction "IP-_5_2") (pintype "bidirectional"))
      (node (ref "U$2") (pin "5_3") (pinfunction "IP-_5_3") (pintype "bidirectional"))
      (node (ref "U$2") (pin "5_4") (pinfunction "IP-_5_4") (pintype "bidirectional"))
      (node (ref "U$2") (pin "5_5") (pinfunction "IP-_5_5") (pintype "bidirectional"))
      (node (ref "U$2") (pin "5_6") (pinfunction "IP-_5_6") (pintype "bidirectional"))
      (node (ref "U$2") (pin "5_7") (pinfunction "IP-_5_7") (pintype "bidirectional"))
      (node (ref "U$2") (pin "5_8") (pinfunction "IP-_5_8") (pintype "bidirectional"))
      (node (ref "U$2") (pin "5_9") (pinfunction "IP-_5_9") (pintype "bidirectional"))
      (node (ref "U$2") (pin "5_B") (pinfunction "IP-_5_B") (pintype "bidirectional"))
      (node (ref "U$2") (pin "5_T") (pinfunction "IP-_5_T") (pintype "bidirectional"))
      (node (ref "U$4") (pin "4_1") (pinfunction "IP+_4_1") (pintype "bidirectional"))
      (node (ref "U$4") (pin "4_10") (pinfunction "IP+_4_10") (pintype "bidirectional"))
      (node (ref "U$4") (pin "4_11") (pinfunction "IP+_4_11") (pintype "bidirectional"))
      (node (ref "U$4") (pin "4_12") (pinfunction "IP+_4_12") (pintype "bidirectional"))
      (node (ref "U$4") (pin "4_13") (pinfunction "IP+_4_13") (pintype "bidirectional"))
      (node (ref "U$4") (pin "4_14") (pinfunction "IP+_4_14") (pintype "bidirectional"))
      (node (ref "U$4") (pin "4_15") (pinfunction "IP+_4_15") (pintype "bidirectional"))
      (node (ref "U$4") (pin "4_16") (pinfunction "IP+_4_16") (pintype "bidirectional"))
      (node (ref "U$4") (pin "4_2") (pinfunction "IP+_4_2") (pintype "bidirectional"))
      (node (ref "U$4") (pin "4_3") (pinfunction "IP+_4_3") (pintype "bidirectional"))
      (node (ref "U$4") (pin "4_4") (pinfunction "IP+_4_4") (pintype "bidirectional"))
      (node (ref "U$4") (pin "4_5") (pinfunction "IP+_4_5") (pintype "bidirectional"))
      (node (ref "U$4") (pin "4_6") (pinfunction "IP+_4_6") (pintype "bidirectional"))
      (node (ref "U$4") (pin "4_7") (pinfunction "IP+_4_7") (pintype "bidirectional"))
      (node (ref "U$4") (pin "4_8") (pinfunction "IP+_4_8") (pintype "bidirectional"))
      (node (ref "U$4") (pin "4_9") (pinfunction "IP+_4_9") (pintype "bidirectional"))
      (node (ref "U$4") (pin "4_B") (pinfunction "IP+_4_B") (pintype "bidirectional"))
      (node (ref "U$4") (pin "4_T") (pinfunction "IP+_4_T") (pintype "bidirectional"))
      (node (ref "U$8") (pin "6") (pinfunction "SENSE_6") (pintype "bidirectional"))
      (node (ref "U$8") (pin "8") (pinfunction "V+_8") (pintype "bidirectional"))
    )
    (net (code "116") (name "Net-(IRLS3034-7P-GATE)") (class "Default")
      (node (ref "IRLS3034-7P") (pin "1") (pinfunction "GATE_1") (pintype "bidirectional"))
      (node (ref "IRLS3034-7P.2") (pin "1") (pinfunction "GATE_1") (pintype "bidirectional"))
      (node (ref "U$8") (pin "5") (pinfunction "GATE_5") (pintype "bidirectional"))
    )
    (net (code "117") (name "Net-(IRLS3034-7P-SOURCE-Pad2)") (class "Default")
      (node (ref "IRLS3034-7P") (pin "2") (pinfunction "SOURCE_2") (pintype "bidirectional"))
      (node (ref "IRLS3034-7P") (pin "3") (pinfunction "SOURCE_3") (pintype "bidirectional"))
      (node (ref "IRLS3034-7P") (pin "4") (pinfunction "SOURCE_4") (pintype "bidirectional"))
      (node (ref "IRLS3034-7P") (pin "5") (pinfunction "SOURCE_5") (pintype "bidirectional"))
      (node (ref "IRLS3034-7P") (pin "6") (pinfunction "SOURCE_6") (pintype "bidirectional"))
      (node (ref "IRLS3034-7P.2") (pin "2") (pinfunction "SOURCE_2") (pintype "bidirectional"))
      (node (ref "IRLS3034-7P.2") (pin "3") (pinfunction "SOURCE_3") (pintype "bidirectional"))
      (node (ref "IRLS3034-7P.2") (pin "4") (pinfunction "SOURCE_4") (pintype "bidirectional"))
      (node (ref "IRLS3034-7P.2") (pin "5") (pinfunction "SOURCE_5") (pintype "bidirectional"))
      (node (ref "IRLS3034-7P.2") (pin "6") (pinfunction "SOURCE_6") (pintype "bidirectional"))
      (node (ref "LED1") (pin "A") (pinfunction "A_A") (pintype "passive"))
      (node (ref "R38") (pin "1") (pinfunction "1_1") (pintype "passive"))
      (node (ref "V_OUT") (pin "P$1") (pinfunction "P$1_P$1") (pintype "bidirectional"))
    )
    (net (code "118") (name "Net-(LED1-PadC)") (class "Default")
      (node (ref "LED1") (pin "C") (pinfunction "C_C") (pintype "passive"))
      (node (ref "R40") (pin "1") (pinfunction "1_1") (pintype "passive"))
    )
    (net (code "119") (name "Net-(LED2-1)") (class "Default")
      (node (ref "LED2") (pin "P$1") (pinfunction "1_P$1") (pintype "bidirectional"))
      (node (ref "R47") (pin "1") (pinfunction "1_1") (pintype "passive"))
    )
    (net (code "120") (name "Net-(LED2-2)") (class "Default")
      (node (ref "LED2") (pin "P$2") (pinfunction "2_P$2") (pintype "bidirectional"))
      (node (ref "R48") (pin "1") (pinfunction "1_1") (pintype "passive"))
    )
    (net (code "121") (name "Net-(LED2-3)") (class "Default")
      (node (ref "LED2") (pin "P$3") (pinfunction "3_P$3") (pintype "bidirectional"))
      (node (ref "R49") (pin "1") (pinfunction "1_1") (pintype "passive"))
    )
    (net (code "122") (name "Net-(LED2-4)") (class "Default")
      (node (ref "LED2") (pin "P$4") (pinfunction "4_P$4") (pintype "bidirectional"))
      (node (ref "R50") (pin "1") (pinfunction "1_1") (pintype "passive"))
    )
    (net (code "123") (name "Net-(LED2-5)") (class "Default")
      (node (ref "LED2") (pin "P$5") (pinfunction "5_P$5") (pintype "bidirectional"))
      (node (ref "R51") (pin "1") (pinfunction "1_1") (pintype "passive"))
    )
    (net (code "124") (name "Net-(LED2-6)") (class "Default")
      (node (ref "LED2") (pin "P$6") (pinfunction "6_P$6") (pintype "bidirectional"))
      (node (ref "R52") (pin "1") (pinfunction "1_1") (pintype "passive"))
    )
    (net (code "125") (name "Net-(LED2-7)") (class "Default")
      (node (ref "LED2") (pin "P$7") (pinfunction "7_P$7") (pintype "bidirectional"))
      (node (ref "R53") (pin "1") (pinfunction "1_1") (pintype "passive"))
    )
    (net (code "126") (name "Net-(LED2-8)") (class "Default")
      (node (ref "LED2") (pin "P$8") (pinfunction "8_P$8") (pintype "bidirectional"))
      (node (ref "R54") (pin "1") (pinfunction "1_1") (pintype "passive"))
    )
    (net (code "127") (name "Net-(LED2-9)") (class "Default")
      (node (ref "LED2") (pin "P$9") (pinfunction "9_P$9") (pintype "bidirectional"))
      (node (ref "R55") (pin "1") (pinfunction "1_1") (pintype "passive"))
    )
    (net (code "128") (name "Net-(LED2-10)") (class "Default")
      (node (ref "LED2") (pin "P$10") (pinfunction "10_P$10") (pintype "bidirectional"))
      (node (ref "R56") (pin "1") (pinfunction "1_1") (pintype "passive"))
    )
    (net (code "129") (name "Net-(Q1-D)") (class "Default")
      (node (ref "Q1") (pin "3") (pinfunction "D_3") (pintype "passive"))
      (node (ref "R2") (pin "P$1") (pinfunction "1_P$1") (pintype "passive"))
      (node (ref "R3") (pin "1") (pinfunction "1_1") (pintype "passive"))
    )
    (net (code "130") (name "Net-(Q1-G)") (class "Default")
      (node (ref "Q1") (pin "1") (pinfunction "G_1") (pintype "passive"))
      (node (ref "R4") (pin "2") (pinfunction "2_2") (pintype "passive"))
    )
    (net (code "131") (name "Net-(Q2-D)") (class "Default")
      (node (ref "Q2") (pin "3") (pinfunction "D_3") (pintype "passive"))
      (node (ref "R6") (pin "P$1") (pinfunction "1_P$1") (pintype "passive"))
      (node (ref "R7") (pin "1") (pinfunction "1_1") (pintype "passive"))
    )
    (net (code "132") (name "Net-(Q2-G)") (class "Default")
      (node (ref "Q2") (pin "1") (pinfunction "G_1") (pintype "passive"))
      (node (ref "R8") (pin "2") (pinfunction "2_2") (pintype "passive"))
    )
    (net (code "133") (name "Net-(Q3-D)") (class "Default")
      (node (ref "Q3") (pin "3") (pinfunction "D_3") (pintype "passive"))
      (node (ref "R10") (pin "P$1") (pinfunction "1_P$1") (pintype "passive"))
      (node (ref "R11") (pin "1") (pinfunction "1_1") (pintype "passive"))
    )
    (net (code "134") (name "Net-(Q3-G)") (class "Default")
      (node (ref "Q3") (pin "1") (pinfunction "G_1") (pintype "passive"))
      (node (ref "R12") (pin "2") (pinfunction "2_2") (pintype "passive"))
    )
    (net (code "135") (name "Net-(Q4-D)") (class "Default")
      (node (ref "Q4") (pin "3") (pinfunction "D_3") (pintype "passive"))
      (node (ref "R14") (pin "P$1") (pinfunction "1_P$1") (pintype "passive"))
      (node (ref "R15") (pin "1") (pinfunction "1_1") (pintype "passive"))
    )
    (net (code "136") (name "Net-(Q4-G)") (class "Default")
      (node (ref "Q4") (pin "1") (pinfunction "G_1") (pintype "passive"))
      (node (ref "R16") (pin "2") (pinfunction "2_2") (pintype "passive"))
    )
    (net (code "137") (name "Net-(Q5-D)") (class "Default")
      (node (ref "Q5") (pin "3") (pinfunction "D_3") (pintype "passive"))
      (node (ref "R18") (pin "P$1") (pinfunction "1_P$1") (pintype "passive"))
      (node (ref "R19") (pin "1") (pinfunction "1_1") (pintype "passive"))
    )
    (net (code "138") (name "Net-(Q5-G)") (class "Default")
      (node (ref "Q5") (pin "1") (pinfunction "G_1") (pintype "passive"))
      (node (ref "R20") (pin "2") (pinfunction "2_2") (pintype "passive"))
    )
    (net (code "139") (name "Net-(Q6-D)") (class "Default")
      (node (ref "Q6") (pin "3") (pinfunction "D_3") (pintype "passive"))
      (node (ref "R22") (pin "P$1") (pinfunction "1_P$1") (pintype "passive"))
      (node (ref "R23") (pin "1") (pinfunction "1_1") (pintype "passive"))
    )
    (net (code "140") (name "Net-(Q6-G)") (class "Default")
      (node (ref "Q6") (pin "1") (pinfunction "G_1") (pintype "passive"))
      (node (ref "R24") (pin "2") (pinfunction "2_2") (pintype "passive"))
    )
    (net (code "141") (name "Net-(Q7-D)") (class "Default")
      (node (ref "Q7") (pin "3") (pinfunction "D_3") (pintype "passive"))
      (node (ref "R26") (pin "P$1") (pinfunction "1_P$1") (pintype "passive"))
      (node (ref "R27") (pin "1") (pinfunction "1_1") (pintype "passive"))
    )
    (net (code "142") (name "Net-(Q7-G)") (class "Default")
      (node (ref "Q7") (pin "1") (pinfunction "G_1") (pintype "passive"))
      (node (ref "R28") (pin "2") (pinfunction "2_2") (pintype "passive"))
    )
    (net (code "143") (name "Net-(Q8-D)") (class "Default")
      (node (ref "Q8") (pin "3") (pinfunction "D_3") (pintype "passive"))
      (node (ref "R30") (pin "P$1") (pinfunction "1_P$1") (pintype "passive"))
      (node (ref "R31") (pin "1") (pinfunction "1_1") (pintype "passive"))
    )
    (net (code "144") (name "Net-(Q8-G)") (class "Default")
      (node (ref "Q8") (pin "1") (pinfunction "G_1") (pintype "passive"))
      (node (ref "R32") (pin "2") (pinfunction "2_2") (pintype "passive"))
    )
    (net (code "145") (name "Net-(Q12-D)") (class "Default")
      (node (ref "Q12") (pin "3") (pinfunction "D_3") (pintype "passive"))
      (node (ref "X1") (pin "1") (pinfunction "S_1") (pintype "passive"))
    )
    (net (code "146") (name "Net-(Q13-D)") (class "Default")
      (node (ref "Q13") (pin "3") (pinfunction "D_3") (pintype "passive"))
      (node (ref "X2") (pin "1") (pinfunction "S_1") (pintype "passive"))
    )
    (net (code "147") (name "Net-(Q14-D)") (class "Default")
      (node (ref "Q14") (pin "3") (pinfunction "D_3") (pintype "passive"))
      (node (ref "X3") (pin "1") (pinfunction "S_1") (pintype "passive"))
    )
    (net (code "148") (name "Net-(Q15-D)") (class "Default")
      (node (ref "Q15") (pin "3") (pinfunction "D_3") (pintype "passive"))
      (node (ref "X4") (pin "1") (pinfunction "S_1") (pintype "passive"))
    )
    (net (code "149") (name "Net-(R72-Pad1)") (class "Default")
      (node (ref "R72") (pin "1") (pinfunction "1_1") (pintype "passive"))
      (node (ref "U$14") (pin "3") (pinfunction "3_3") (pintype "bidirectional"))
      (node (ref "U$15") (pin "A") (pinfunction "A_A") (pintype "bidirectional"))
    )
    (net (code "150") (name "Net-(R72-Pad2)") (class "Default")
      (node (ref "R72") (pin "2") (pinfunction "2_2") (pintype "passive"))
      (node (ref "U$14") (pin "6") (pinfunction "6_6") (pintype "bidirectional"))
      (node (ref "U$15") (pin "B") (pinfunction "B_B") (pintype "bidirectional"))
    )
    (net (code "151") (name "Net-(R73-Pad1)") (class "Default")
      (node (ref "R73") (pin "1") (pinfunction "1_1") (pintype "passive"))
      (node (ref "U$14") (pin "2") (pinfunction "2_2") (pintype "bidirectional"))
      (node (ref "U$15") (pin "Z") (pinfunction "Z_Z") (pintype "bidirectional"))
    )
    (net (code "152") (name "Net-(R73-Pad2)") (class "Default")
      (node (ref "R73") (pin "2") (pinfunction "2_2") (pintype "passive"))
      (node (ref "U$14") (pin "1") (pinfunction "1_1") (pintype "bidirectional"))
      (node (ref "U$15") (pin "Y") (pinfunction "Y_Y") (pintype "bidirectional"))
    )
    (net (code "153") (name "Net-(S1-P)") (class "Default")
      (node (ref "F1") (pin "P$1") (pinfunction "P$1_P$1") (pintype "bidirectional"))
      (node (ref "S1") (pin "2") (pinfunction "P_2") (pintype "passive"))
    )
    (net (code "154") (name "Net-(THERM_1A-S)") (class "Default")
      (node (ref "R33") (pin "2") (pinfunction "2_2") (pintype "passive"))
      (node (ref "R34") (pin "2") (pinfunction "2_2") (pintype "passive"))
      (node (ref "THERM_1") (pin "1") (pinfunction "S_1") (pintype "passive"))
    )
    (net (code "155") (name "Net-(THERM_2A-S)") (class "Default")
      (node (ref "R35") (pin "2") (pinfunction "2_2") (pintype "passive"))
      (node (ref "R36") (pin "2") (pinfunction "2_2") (pintype "passive"))
      (node (ref "THERM_2") (pin "1") (pinfunction "S_1") (pintype "passive"))
    )
    (net (code "156") (name "Net-(U$1-S1)") (class "Default")
      (node (ref "R4") (pin "1") (pinfunction "1_1") (pintype "passive"))
      (node (ref "U$1") (pin "25") (pinfunction "S1_25") (pintype "bidirectional"))
    )
    (net (code "157") (name "Net-(U$1-V+)") (class "Default")
      (node (ref "C13") (pin "1") (pinfunction "1_1") (pintype "passive"))
      (node (ref "R37") (pin "1") (pinfunction "1_1") (pintype "passive"))
      (node (ref "U$1") (pin "1") (pinfunction "V+_1") (pintype "bidirectional"))
    )
    (net (code "158") (name "Net-(U$5-1)") (class "Default")
      (node (ref "U$3") (pin "+") (pinfunction "+_+") (pintype "passive"))
      (node (ref "U$4") (pin "5_1") (pinfunction "IP-_5_1") (pintype "bidirectional"))
      (node (ref "U$4") (pin "5_10") (pinfunction "IP-_5_10") (pintype "bidirectional"))
      (node (ref "U$4") (pin "5_11") (pinfunction "IP-_5_11") (pintype "bidirectional"))
      (node (ref "U$4") (pin "5_12") (pinfunction "IP-_5_12") (pintype "bidirectional"))
      (node (ref "U$4") (pin "5_13") (pinfunction "IP-_5_13") (pintype "bidirectional"))
      (node (ref "U$4") (pin "5_14") (pinfunction "IP-_5_14") (pintype "bidirectional"))
      (node (ref "U$4") (pin "5_15") (pinfunction "IP-_5_15") (pintype "bidirectional"))
      (node (ref "U$4") (pin "5_16") (pinfunction "IP-_5_16") (pintype "bidirectional"))
      (node (ref "U$4") (pin "5_2") (pinfunction "IP-_5_2") (pintype "bidirectional"))
      (node (ref "U$4") (pin "5_3") (pinfunction "IP-_5_3") (pintype "bidirectional"))
      (node (ref "U$4") (pin "5_4") (pinfunction "IP-_5_4") (pintype "bidirectional"))
      (node (ref "U$4") (pin "5_5") (pinfunction "IP-_5_5") (pintype "bidirectional"))
      (node (ref "U$4") (pin "5_6") (pinfunction "IP-_5_6") (pintype "bidirectional"))
      (node (ref "U$4") (pin "5_7") (pinfunction "IP-_5_7") (pintype "bidirectional"))
      (node (ref "U$4") (pin "5_8") (pinfunction "IP-_5_8") (pintype "bidirectional"))
      (node (ref "U$4") (pin "5_9") (pinfunction "IP-_5_9") (pintype "bidirectional"))
      (node (ref "U$4") (pin "5_B") (pinfunction "IP-_5_B") (pintype "bidirectional"))
      (node (ref "U$4") (pin "5_T") (pinfunction "IP-_5_T") (pintype "bidirectional"))
      (node (ref "U$5") (pin "P$1") (pinfunction "1_P$1") (pintype "passive"))
      (node (ref "U$6") (pin "+") (pinfunction "+_+") (pintype "passive"))
      (node (ref "U$7") (pin "+") (pinfunction "+_+") (pintype "passive"))
    )
    (net (code "159") (name "Net-(U$16-G)") (class "Default")
      (node (ref "U$16") (pin "P$4") (pinfunction "G_P$4") (pintype "bidirectional"))
      (node (ref "U$18") (pin "P$7") (pinfunction "TG_P$7") (pintype "bidirectional"))
    )
    (net (code "160") (name "Net-(U$16-S1)") (class "Default")
      (node (ref "C15") (pin "2") (pinfunction "2_2") (pintype "passive"))
      (node (ref "U$16") (pin "P$1") (pinfunction "S1_P$1") (pintype "bidirectional"))
      (node (ref "U$16") (pin "P$2") (pinfunction "S2_P$2") (pintype "bidirectional"))
      (node (ref "U$16") (pin "P$3") (pinfunction "S3_P$3") (pintype "bidirectional"))
      (node (ref "U$17") (pin "P$5") (pinfunction "D1_P$5") (pintype "bidirectional"))
      (node (ref "U$17") (pin "P$6") (pinfunction "D2_P$6") (pintype "bidirectional"))
      (node (ref "U$17") (pin "P$7") (pinfunction "D3_P$7") (pintype "bidirectional"))
      (node (ref "U$17") (pin "P$8") (pinfunction "D4_P$8") (pintype "bidirectional"))
      (node (ref "U$17") (pin "P$9") (pinfunction "D1_P$9") (pintype "bidirectional"))
      (node (ref "U$18") (pin "P$8") (pinfunction "TS_P$8") (pintype "bidirectional"))
      (node (ref "U$5") (pin "P$2") (pinfunction "2_P$2") (pintype "passive"))
      (node (ref "U$9") (pin "P$2") (pinfunction "C_P$2") (pintype "passive"))
    )
    (net (code "161") (name "Net-(U$17-G)") (class "Default")
      (node (ref "U$17") (pin "P$4") (pinfunction "G_P$4") (pintype "bidirectional"))
      (node (ref "U$18") (pin "P$4") (pinfunction "BG_P$4") (pintype "bidirectional"))
    )
    (net (code "162") (name "unconnected-(IC2-DRAIN10-PadP$17)") (class "Default")
      (node (ref "IC2") (pin "P$17") (pinfunction "DRAIN10_P$17") (pintype "bidirectional"))
    )
    (net (code "163") (name "unconnected-(IC2-DRAIN11-PadP$18)") (class "Default")
      (node (ref "IC2") (pin "P$18") (pinfunction "DRAIN11_P$18") (pintype "bidirectional"))
    )
    (net (code "164") (name "unconnected-(IC2-SER_OUT-PadP$11)") (class "Default")
      (node (ref "IC2") (pin "P$11") (pinfunction "SER_OUT_P$11") (pintype "bidirectional"))
    )
    (net (code "165") (name "unconnected-(U$1-MMB-Pad33)") (class "Default")
      (node (ref "U$1") (pin "33") (pinfunction "MMB_33") (pintype "bidirectional"))
    )
    (net (code "166") (name "unconnected-(U$1-NC-Pad27)") (class "Default")
      (node (ref "U$1") (pin "27") (pinfunction "NC_27") (pintype "bidirectional"))
    )
    (net (code "167") (name "unconnected-(U$1-S9-Pad9)") (class "Default")
      (node (ref "U$1") (pin "9") (pinfunction "S9_9") (pintype "bidirectional"))
    )
    (net (code "168") (name "unconnected-(U$1-S10-Pad7)") (class "Default")
      (node (ref "U$1") (pin "7") (pinfunction "S10_7") (pintype "bidirectional"))
    )
    (net (code "169") (name "unconnected-(U$1-S11-Pad5)") (class "Default")
      (node (ref "U$1") (pin "5") (pinfunction "S11_5") (pintype "bidirectional"))
    )
    (net (code "170") (name "unconnected-(U$1-S12-Pad3)") (class "Default")
      (node (ref "U$1") (pin "3") (pinfunction "S12_3") (pintype "bidirectional"))
    )
    (net (code "171") (name "unconnected-(U$1-WDTB-Pad34)") (class "Default")
      (node (ref "U$1") (pin "34") (pinfunction "WDTB_34") (pintype "bidirectional"))
    )
    (net (code "172") (name "unconnected-(U$8-FAULT-Pad3)") (class "Default")
      (node (ref "U$8") (pin "3") (pinfunction "FAULT_3") (pintype "bidirectional"))
    )
    (net (code "173") (name "unconnected-(U$8-TIMER-Pad2)") (class "Default")
      (node (ref "U$8") (pin "2") (pinfunction "TIMER_2") (pintype "bidirectional"))
    )
    (net (code "174") (name "unconnected-(U$13-P6.1-Pad6.1)") (class "Default")
      (node (ref "U$13") (pin "6.1") (pinfunction "P6.1_6.1") (pintype "bidirectional"))
    )
    (net (code "175") (name "unconnected-(U$13-P6.7-Pad6.7)") (class "Default")
      (node (ref "U$13") (pin "6.7") (pinfunction "P6.7_6.7") (pintype "bidirectional"))
    )
    (net (code "176") (name "unconnected-(U$13-P7.0-Pad7.0)") (class "Default")
      (node (ref "U$13") (pin "7.0") (pinfunction "P7.0_7.0") (pintype "bidirectional"))
    )
    (net (code "177") (name "unconnected-(U$13-P7.1-Pad7.1)") (class "Default")
      (node (ref "U$13") (pin "7.1") (pinfunction "P7.1_7.1") (pintype "bidirectional"))
    )
    (net (code "178") (name "unconnected-(U$13-P7.2-Pad7.2)") (class "Default")
      (node (ref "U$13") (pin "7.2") (pinfunction "P7.2_7.2") (pintype "bidirectional"))
    )
    (net (code "179") (name "unconnected-(U$13-P7.3-Pad7.3)") (class "Default")
      (node (ref "U$13") (pin "7.3") (pinfunction "P7.3_7.3") (pintype "bidirectional"))
    )
    (net (code "180") (name "unconnected-(U$13-P7.4-Pad7.4)") (class "Default")
      (node (ref "U$13") (pin "7.4") (pinfunction "P7.4_7.4") (pintype "bidirectional"))
    )
    (net (code "181") (name "unconnected-(U$13-P7.5-Pad7.5)") (class "Default")
      (node (ref "U$13") (pin "7.5") (pinfunction "P7.5_7.5") (pintype "bidirectional"))
    )
    (net (code "182") (name "unconnected-(U$13-P7.7-Pad7.7)") (class "Default")
      (node (ref "U$13") (pin "7.7") (pinfunction "P7.7_7.7") (pintype "bidirectional"))
    )
    (net (code "183") (name "unconnected-(U$13-P8.2-Pad8.2)") (class "Default")
      (node (ref "U$13") (pin "8.2") (pinfunction "P8.2_8.2") (pintype "bidirectional"))
    )
    (net (code "184") (name "unconnected-(U$13-P8.3-Pad8.3)") (class "Default")
      (node (ref "U$13") (pin "8.3") (pinfunction "P8.3_8.3") (pintype "bidirectional"))
    )
    (net (code "185") (name "unconnected-(U$13-P8.4-Pad8.4)") (class "Default")
      (node (ref "U$13") (pin "8.4") (pinfunction "P8.4_8.4") (pintype "bidirectional"))
    )
    (net (code "186") (name "unconnected-(U$13-P8.5-Pad8.5)") (class "Default")
      (node (ref "U$13") (pin "8.5") (pinfunction "P8.5_8.5") (pintype "bidirectional"))
    )
    (net (code "187") (name "unconnected-(U$13-P8.6-Pad8.6)") (class "Default")
      (node (ref "U$13") (pin "8.6") (pinfunction "P8.6_8.6") (pintype "bidirectional"))
    )
    (net (code "188") (name "unconnected-(U$13-P8.7-Pad8.7)") (class "Default")
      (node (ref "U$13") (pin "8.7") (pinfunction "P8.7_8.7") (pintype "bidirectional"))
    )
    (net (code "189") (name "unconnected-(U$13-P9.0-Pad9.0)") (class "Default")
      (node (ref "U$13") (pin "9.0") (pinfunction "P9.0_9.0") (pintype "bidirectional"))
    )
    (net (code "190") (name "unconnected-(U$13-P9.1-Pad9.1)") (class "Default")
      (node (ref "U$13") (pin "9.1") (pinfunction "P9.1_9.1") (pintype "bidirectional"))
    )
    (net (code "191") (name "unconnected-(U$13-P9.2-Pad9.2)") (class "Default")
      (node (ref "U$13") (pin "9.2") (pinfunction "P9.2_9.2") (pintype "bidirectional"))
    )
    (net (code "192") (name "unconnected-(U$13-P9.3-Pad9.3)") (class "Default")
      (node (ref "U$13") (pin "9.3") (pinfunction "P9.3_9.3") (pintype "bidirectional"))
    )
    (net (code "193") (name "unconnected-(U$13-P9.4-Pad9.4)") (class "Default")
      (node (ref "U$13") (pin "9.4") (pinfunction "P9.4_9.4") (pintype "bidirectional"))
    )
    (net (code "194") (name "unconnected-(U$13-P9.5-Pad9.5)") (class "Default")
      (node (ref "U$13") (pin "9.5") (pinfunction "P9.5_9.5") (pintype "bidirectional"))
    )
    (net (code "195") (name "unconnected-(U$13-P10.4-Pad10.4)") (class "Default")
      (node (ref "U$13") (pin "10.4") (pinfunction "P10.4_10.4") (pintype "bidirectional"))
    )
    (net (code "196") (name "unconnected-(U$13-P10.5-Pad10.5)") (class "Default")
      (node (ref "U$13") (pin "10.5") (pinfunction "P10.5_10.5") (pintype "bidirectional"))
    )
    (net (code "197") (name "unconnected-(U$13-{slash}RST-PadRST)") (class "Default")
      (node (ref "U$13") (pin "RST") (pinfunction "/RST_RST") (pintype "bidirectional"))
    )
    (net (code "198") (name "unconnected-(U$14-Pad4)") (class "Default")
      (node (ref "U$14") (pin "4") (pinfunction "4_4") (pintype "bidirectional"))
    )
    (net (code "199") (name "unconnected-(U$14-Pad5)") (class "Default")
      (node (ref "U$14") (pin "5") (pinfunction "5_5") (pintype "bidirectional"))
    )
    (net (code "200") (name "unconnected-(U$18-NC-PadP$5)") (class "Default")
      (node (ref "U$18") (pin "P$5") (pinfunction "NC_P$5") (pintype "bidirectional"))
    )
  )
)
